# ArduHub.net
KiCad netlist of a schematic drawn in EAGLE
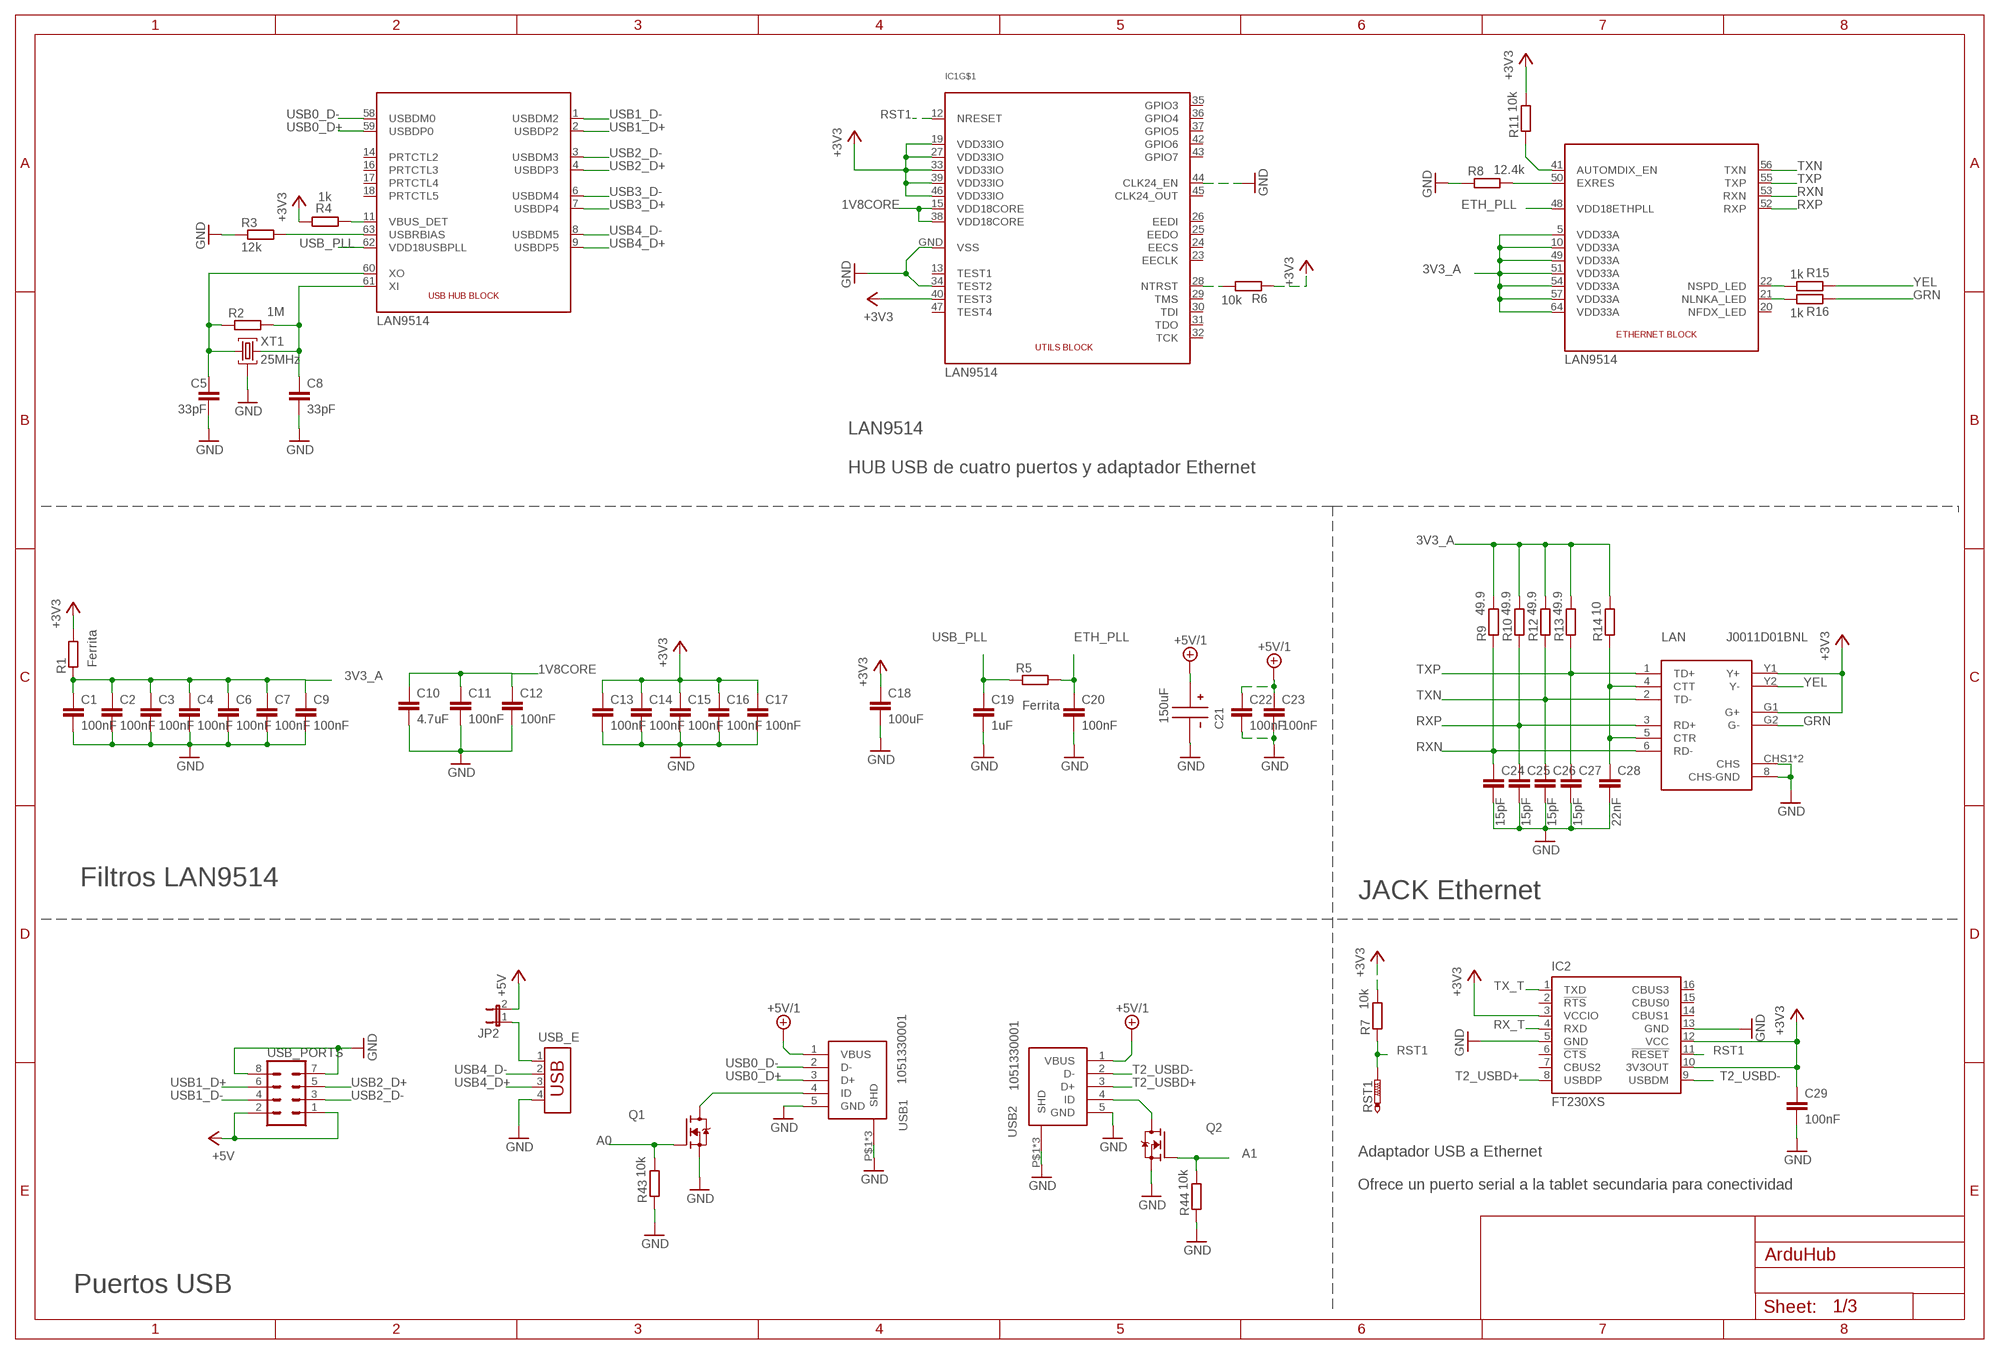
[diagram p0: schematic, sheet 1]
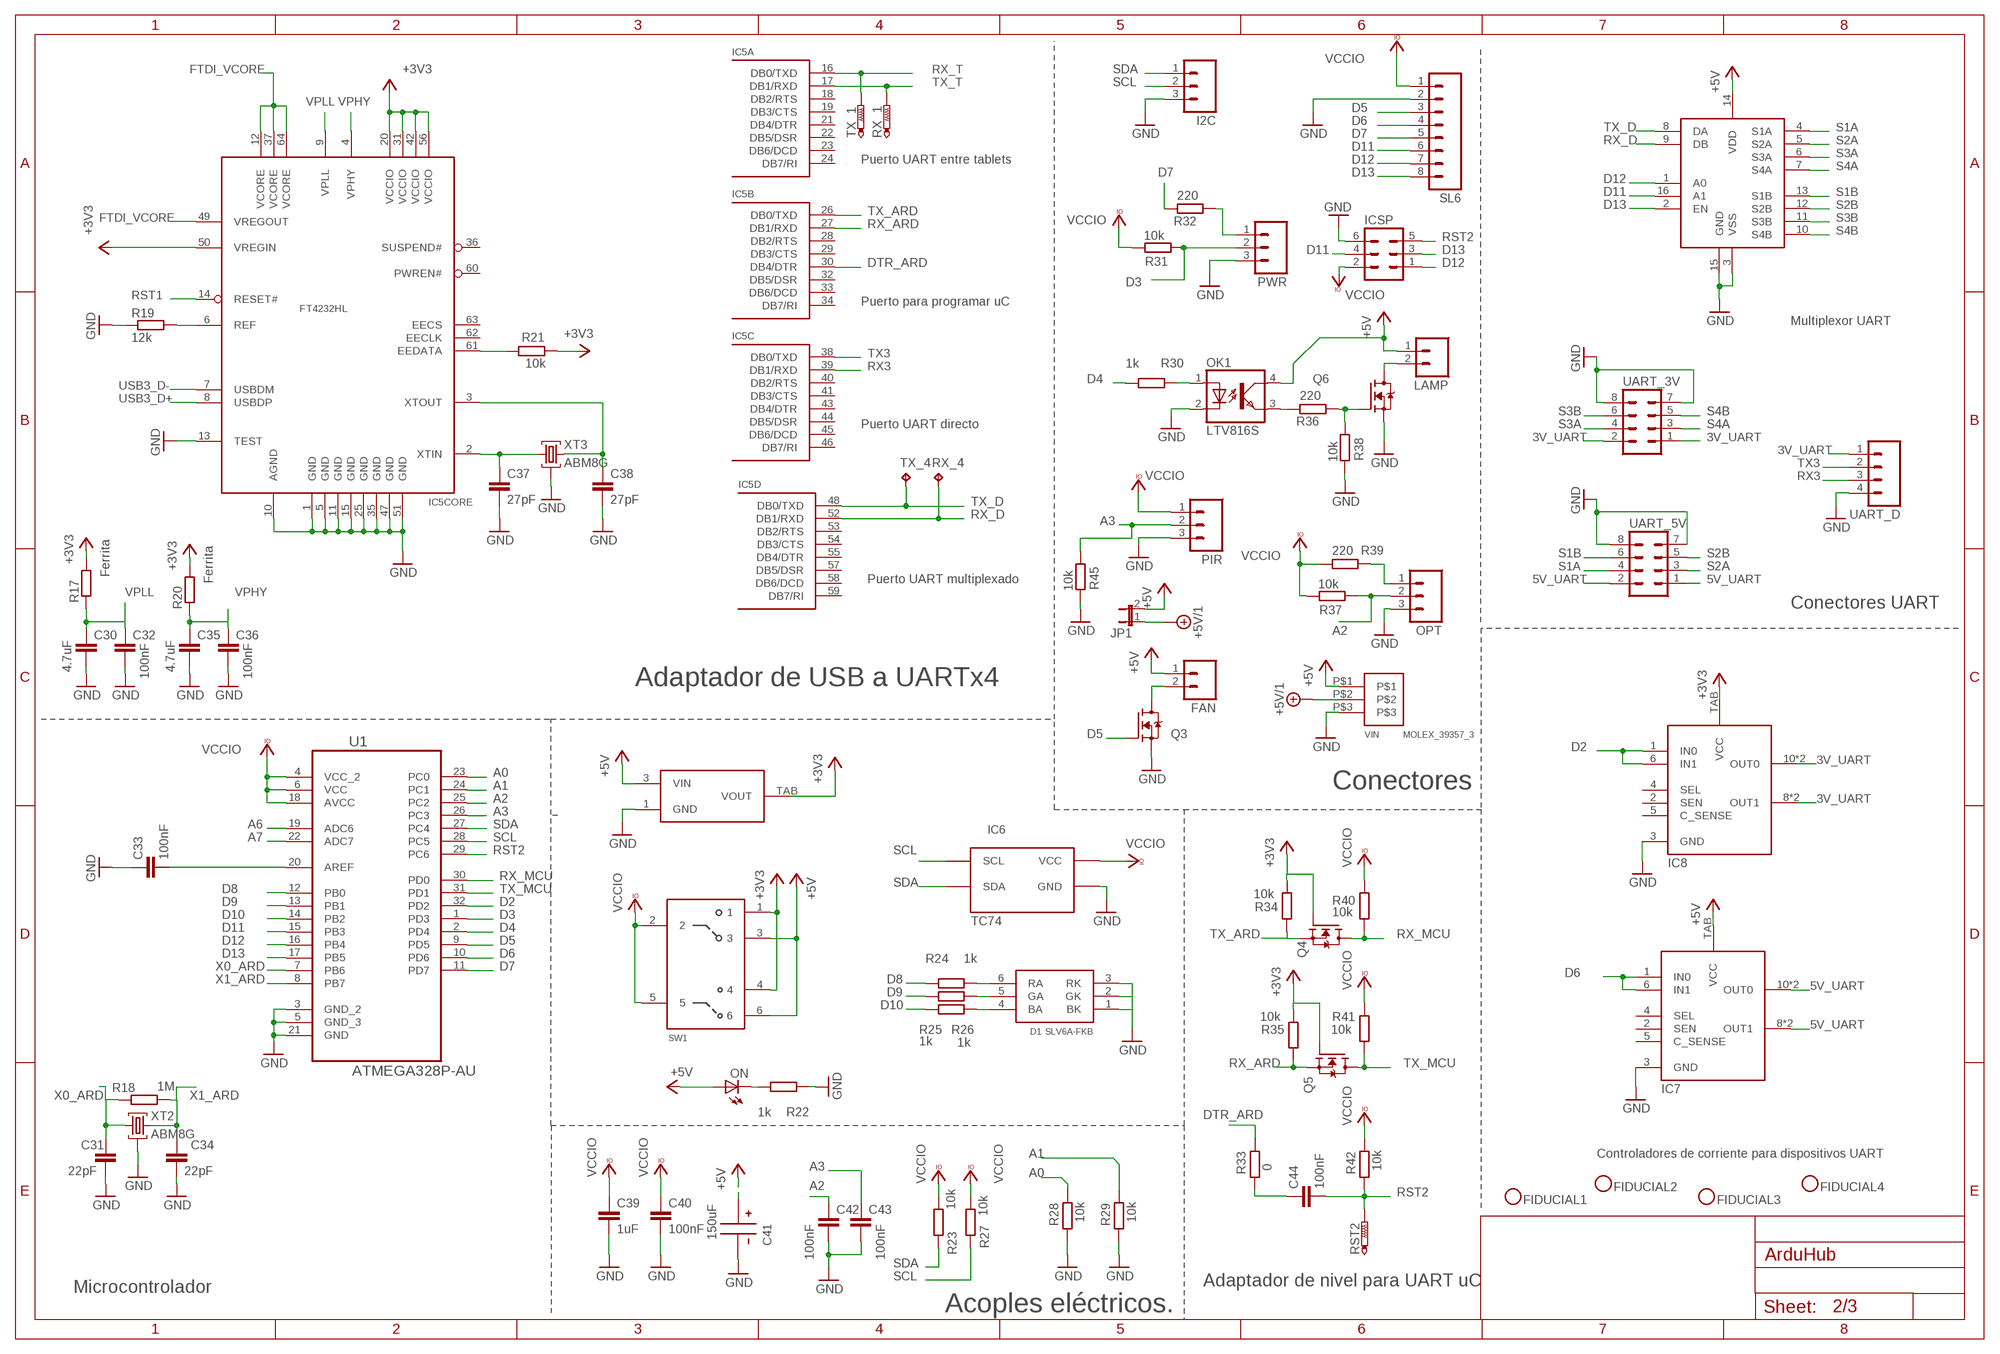
[diagram p1: schematic, sheet 2]
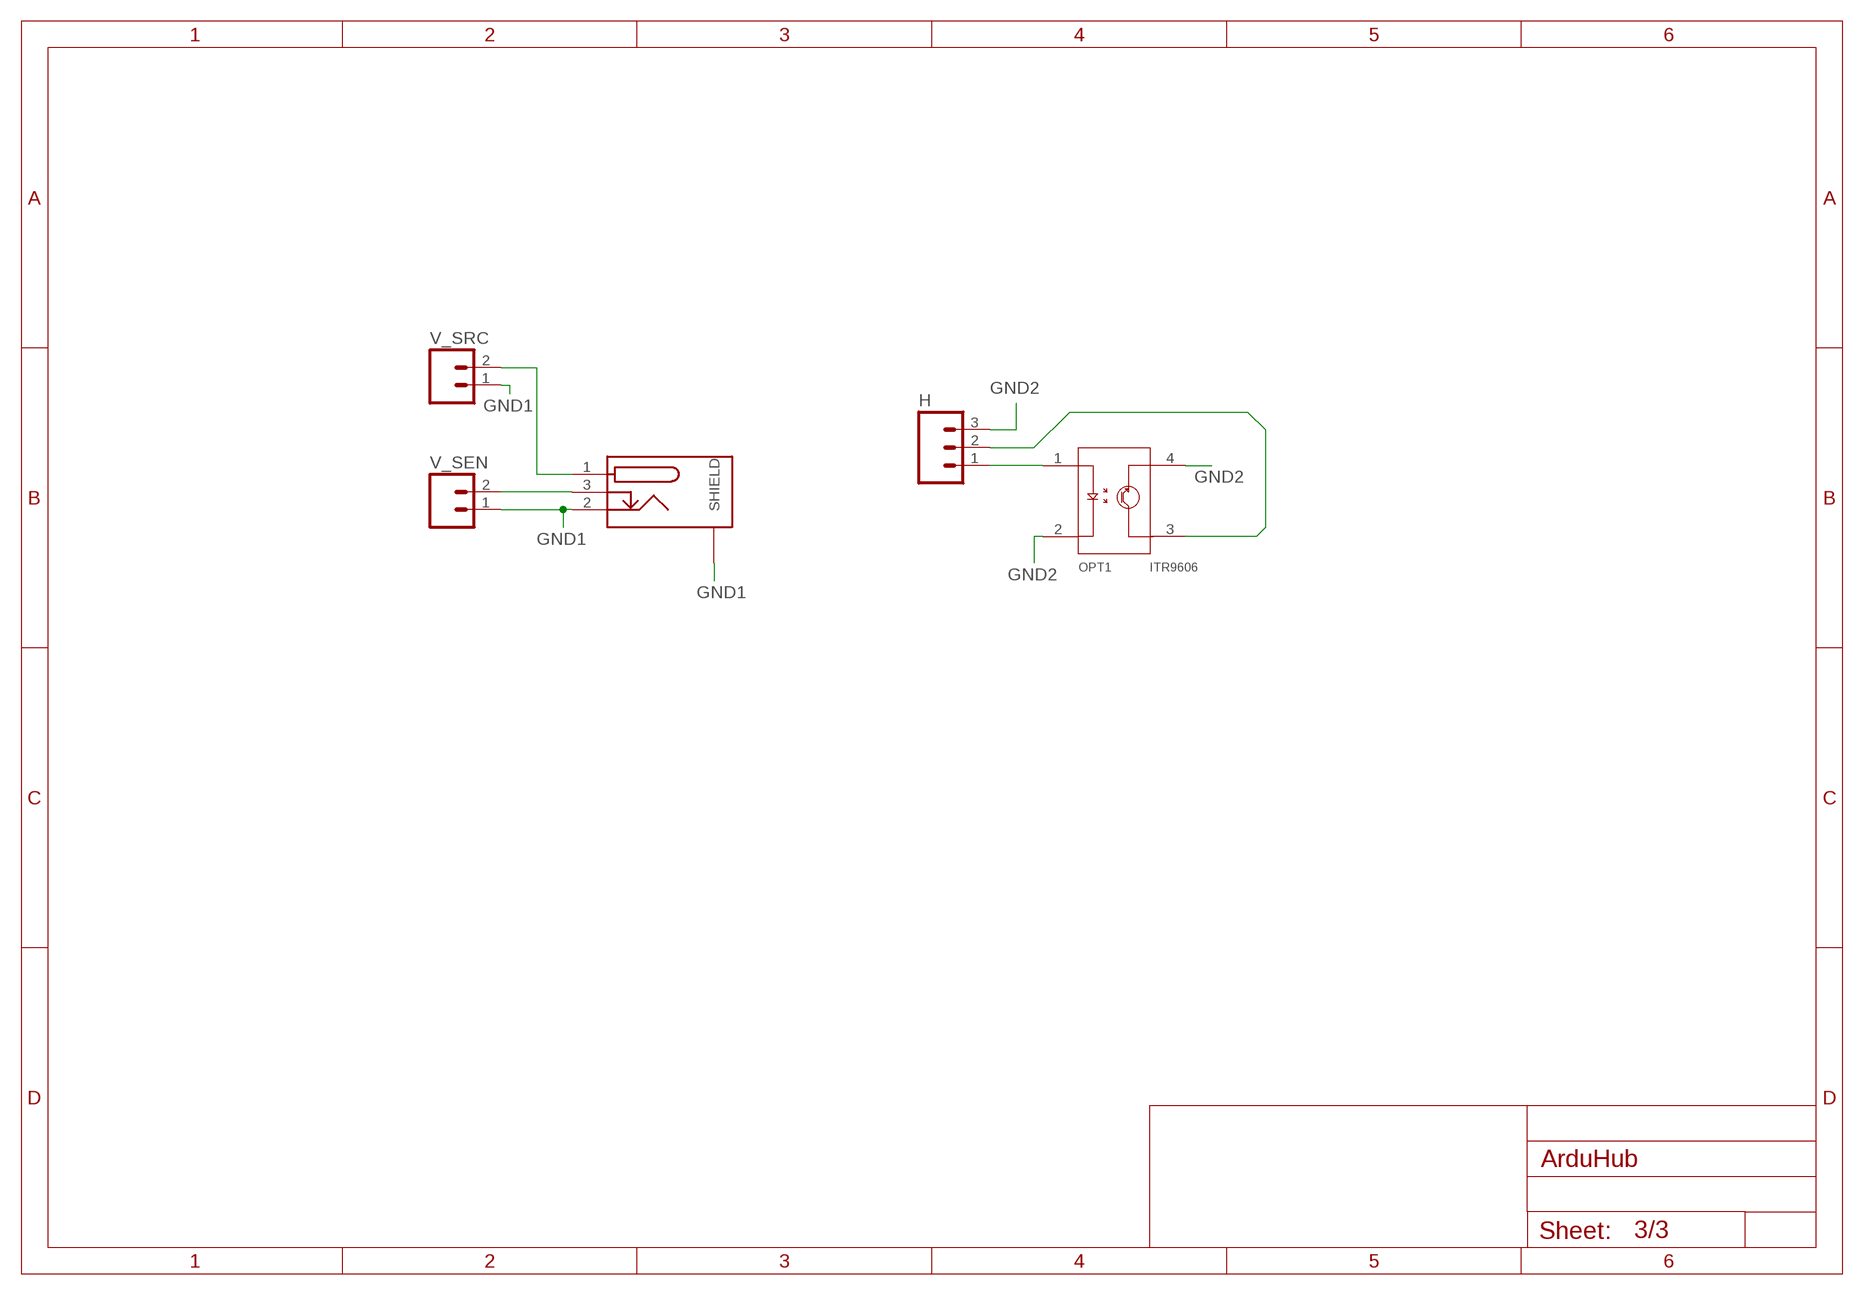
[diagram p2: schematic, sheet 3]

(export (version "E")
  (design (tool "Eeschema 10.0.6"))
  (components
    (comp (ref "C30")
      (value "4.7uF")
      (footprint "eagle-import:C0402")
      (libsource (lib "eagle-import") (part "C-EUC0402"))
    )
    (comp (ref "C31")
      (value "22pF")
      (footprint "eagle-import:C0402")
      (libsource (lib "eagle-import") (part "C-EUC0402"))
    )
    (comp (ref "C32")
      (value "100nF")
      (footprint "eagle-import:C0402")
      (libsource (lib "eagle-import") (part "C-EUC0402"))
    )
    (comp (ref "C33")
      (value "100nF")
      (footprint "eagle-import:C0402")
      (libsource (lib "eagle-import") (part "C-EUC0402"))
    )
    (comp (ref "C34")
      (value "22pF")
      (footprint "eagle-import:C0402")
      (libsource (lib "eagle-import") (part "C-EUC0402"))
    )
    (comp (ref "C35")
      (value "4.7uF")
      (footprint "eagle-import:C0402")
      (libsource (lib "eagle-import") (part "C-EUC0402"))
    )
    (comp (ref "C36")
      (value "100nF")
      (footprint "eagle-import:C0402")
      (libsource (lib "eagle-import") (part "C-EUC0402"))
    )
    (comp (ref "C37")
      (value "27pF")
      (footprint "eagle-import:C0402")
      (libsource (lib "eagle-import") (part "C-EUC0402"))
    )
    (comp (ref "C38")
      (value "27pF")
      (footprint "eagle-import:C0402")
      (libsource (lib "eagle-import") (part "C-EUC0402"))
    )
    (comp (ref "C39")
      (value "1uF")
      (footprint "eagle-import:C0402")
      (libsource (lib "eagle-import") (part "C-EUC0402"))
    )
    (comp (ref "C40")
      (value "100nF")
      (footprint "eagle-import:C0402")
      (libsource (lib "eagle-import") (part "C-EUC0402"))
    )
    (comp (ref "C41")
      (value "150uF")
      (footprint "eagle-import:MVA_CAP_F55")
      (libsource (lib "eagle-import") (part "EMVE100ADA151MF55G"))
    )
    (comp (ref "C42")
      (value "100nF")
      (footprint "eagle-import:C0402")
      (libsource (lib "eagle-import") (part "C-EUC0402"))
    )
    (comp (ref "C43")
      (value "100nF")
      (footprint "eagle-import:C0402")
      (libsource (lib "eagle-import") (part "C-EUC0402"))
    )
    (comp (ref "C44")
      (value "100nF")
      (footprint "eagle-import:C0402")
      (libsource (lib "eagle-import") (part "C-EUC0402"))
    )
    (comp (ref "D1")
      (value "SLV6A-FKB")
      (footprint "eagle-import:PLCC-6")
      (libsource (lib "eagle-import") (part "SLV6A-FKB"))
    )
    (comp (ref "FAN")
      (value "M02")
      (footprint "eagle-import:02P")
      (libsource (lib "eagle-import") (part "M02"))
    )
    (comp (ref "FIDUCIAL1")
      (value "FIDU_2C")
      (footprint "eagle-import:FIDUCIAL_TEST_2C")
      (libsource (lib "eagle-import") (part "FIDU_2C"))
    )
    (comp (ref "FIDUCIAL2")
      (value "FIDU_2C")
      (footprint "eagle-import:FIDUCIAL_TEST_2C")
      (libsource (lib "eagle-import") (part "FIDU_2C"))
    )
    (comp (ref "FIDUCIAL3")
      (value "FIDU_2C")
      (footprint "eagle-import:FIDUCIAL_TEST_2C")
      (libsource (lib "eagle-import") (part "FIDU_2C"))
    )
    (comp (ref "FIDUCIAL4")
      (value "FIDU_2C")
      (footprint "eagle-import:FIDUCIAL_TEST_2C")
      (libsource (lib "eagle-import") (part "FIDU_2C"))
    )
    (comp (ref "I2C")
      (value "M03")
      (footprint "eagle-import:03P")
      (libsource (lib "eagle-import") (part "M03"))
    )
    (comp (ref "IC4")
      (value "AP1084D")
      (footprint "eagle-import:TO_252_3")
      (libsource (lib "eagle-import") (part "AP1084D"))
    )
    (comp (ref "IC5")
      (value "FT4232HL")
      (footprint "eagle-import:LQFP64")
      (fields (field (name "REF") "FT4232HL-REEL"))
      (libsource (lib "eagle-import") (part "FT4232HL"))
    )
    (comp (ref "IC6")
      (value "TC74")
      (footprint "eagle-import:SOT-23-5")
      (libsource (lib "eagle-import") (part "TC74"))
    )
    (comp (ref "IC7")
      (value "VND7140AJ12TR")
      (footprint "eagle-import:POWERSSO-12")
      (libsource (lib "eagle-import") (part "VND7140AJ12TR"))
    )
    (comp (ref "IC8")
      (value "VND7140AJ12TR")
      (footprint "eagle-import:POWERSSO-12")
      (libsource (lib "eagle-import") (part "VND7140AJ12TR"))
    )
    (comp (ref "IC9")
      (value "MUX509IPWR")
      (footprint "eagle-import:TSSOP-16")
      (libsource (lib "eagle-import") (part "MUX509IPWR"))
    )
    (comp (ref "ICSP")
      (value "MA03-2")
      (footprint "eagle-import:MA03-2")
      (libsource (lib "eagle-import") (part "MA03-2"))
    )
    (comp (ref "JP1")
      (value "JP1E")
      (footprint "eagle-import:JP1")
      (libsource (lib "eagle-import") (part "JP1E"))
    )
    (comp (ref "LAMP")
      (value "M02")
      (footprint "eagle-import:02P")
      (libsource (lib "eagle-import") (part "M02"))
    )
    (comp (ref "OK1")
      (value "LTV816S")
      (footprint "eagle-import:SMD4")
      (libsource (lib "eagle-import") (part "LTV816S"))
    )
    (comp (ref "ON")
      (value "LED-0603")
      (footprint "eagle-import:LED-603")
      (libsource (lib "eagle-import") (part "LED-0603"))
    )
    (comp (ref "OPT")
      (value "M03")
      (footprint "eagle-import:03P")
      (libsource (lib "eagle-import") (part "M03"))
    )
    (comp (ref "PIR")
      (value "M03")
      (footprint "eagle-import:03P")
      (libsource (lib "eagle-import") (part "M03"))
    )
    (comp (ref "PWR")
      (value "M03")
      (footprint "eagle-import:03P")
      (libsource (lib "eagle-import") (part "M03"))
    )
    (comp (ref "Q3")
      (value "TRANSISTOR_FET_BS170-SOT-23")
      (footprint "eagle-import:SOT-23")
      (libsource (lib "eagle-import") (part "TRANSISTOR_FET_BS170-SOT-23"))
    )
    (comp (ref "Q4")
      (value "TRANSISTOR_FET_BS170-SOT-23")
      (footprint "eagle-import:SOT-23")
      (libsource (lib "eagle-import") (part "TRANSISTOR_FET_BS170-SOT-23"))
    )
    (comp (ref "Q5")
      (value "TRANSISTOR_FET_BS170-SOT-23")
      (footprint "eagle-import:SOT-23")
      (libsource (lib "eagle-import") (part "TRANSISTOR_FET_BS170-SOT-23"))
    )
    (comp (ref "Q6")
      (value "TRANSISTOR_FET_BS170-SOT-23")
      (footprint "eagle-import:SOT-23")
      (libsource (lib "eagle-import") (part "TRANSISTOR_FET_BS170-SOT-23"))
    )
    (comp (ref "R17")
      (value "Ferrita")
      (footprint "eagle-import:R0603")
      (libsource (lib "eagle-import") (part "R-EU_R0603"))
    )
    (comp (ref "R18")
      (value "1M")
      (footprint "eagle-import:R0402")
      (libsource (lib "eagle-import") (part "R-EU_R0402"))
    )
    (comp (ref "R19")
      (value "12k")
      (footprint "eagle-import:R0402")
      (libsource (lib "eagle-import") (part "R-EU_R0402"))
    )
    (comp (ref "R20")
      (value "Ferrita")
      (footprint "eagle-import:R0603")
      (libsource (lib "eagle-import") (part "R-EU_R0603"))
    )
    (comp (ref "R21")
      (value "10k")
      (footprint "eagle-import:R0402")
      (libsource (lib "eagle-import") (part "R-EU_R0402"))
    )
    (comp (ref "R22")
      (value "1k")
      (footprint "eagle-import:R0402")
      (libsource (lib "eagle-import") (part "R-EU_R0402"))
    )
    (comp (ref "R23")
      (value "10k")
      (footprint "eagle-import:R0402")
      (libsource (lib "eagle-import") (part "R-EU_R0402"))
    )
    (comp (ref "R24")
      (value "1k")
      (footprint "eagle-import:R0402")
      (libsource (lib "eagle-import") (part "R-EU_R0402"))
    )
    (comp (ref "R25")
      (value "1k")
      (footprint "eagle-import:R0402")
      (libsource (lib "eagle-import") (part "R-EU_R0402"))
    )
    (comp (ref "R26")
      (value "1k")
      (footprint "eagle-import:R0402")
      (libsource (lib "eagle-import") (part "R-EU_R0402"))
    )
    (comp (ref "R27")
      (value "10k")
      (footprint "eagle-import:R0402")
      (libsource (lib "eagle-import") (part "R-EU_R0402"))
    )
    (comp (ref "R28")
      (value "10k")
      (footprint "eagle-import:R0402")
      (libsource (lib "eagle-import") (part "R-EU_R0402"))
    )
    (comp (ref "R29")
      (value "10k")
      (footprint "eagle-import:R0402")
      (libsource (lib "eagle-import") (part "R-EU_R0402"))
    )
    (comp (ref "R30")
      (value "1k")
      (footprint "eagle-import:R0402")
      (libsource (lib "eagle-import") (part "R-EU_R0402"))
    )
    (comp (ref "R31")
      (value "10k")
      (footprint "eagle-import:R0402")
      (libsource (lib "eagle-import") (part "R-EU_R0402"))
    )
    (comp (ref "R32")
      (value "220")
      (footprint "eagle-import:R0402")
      (libsource (lib "eagle-import") (part "R-EU_R0402"))
    )
    (comp (ref "R33")
      (value "0")
      (footprint "eagle-import:R0402")
      (libsource (lib "eagle-import") (part "R-EU_R0402"))
    )
    (comp (ref "R34")
      (value "10k")
      (footprint "eagle-import:R0402")
      (libsource (lib "eagle-import") (part "R-EU_R0402"))
    )
    (comp (ref "R35")
      (value "10k")
      (footprint "eagle-import:R0402")
      (libsource (lib "eagle-import") (part "R-EU_R0402"))
    )
    (comp (ref "R36")
      (value "220")
      (footprint "eagle-import:R0402")
      (libsource (lib "eagle-import") (part "R-EU_R0402"))
    )
    (comp (ref "R37")
      (value "10k")
      (footprint "eagle-import:R0402")
      (libsource (lib "eagle-import") (part "R-EU_R0402"))
    )
    (comp (ref "R38")
      (value "10k")
      (footprint "eagle-import:R0402")
      (libsource (lib "eagle-import") (part "R-EU_R0402"))
    )
    (comp (ref "R39")
      (value "220")
      (footprint "eagle-import:R0402")
      (libsource (lib "eagle-import") (part "R-EU_R0402"))
    )
    (comp (ref "R40")
      (value "10k")
      (footprint "eagle-import:R0402")
      (libsource (lib "eagle-import") (part "R-EU_R0402"))
    )
    (comp (ref "R41")
      (value "10k")
      (footprint "eagle-import:R0402")
      (libsource (lib "eagle-import") (part "R-EU_R0402"))
    )
    (comp (ref "R42")
      (value "10k")
      (footprint "eagle-import:R0402")
      (libsource (lib "eagle-import") (part "R-EU_R0402"))
    )
    (comp (ref "R45")
      (value "10k")
      (footprint "eagle-import:R0402")
      (libsource (lib "eagle-import") (part "R-EU_R0402"))
    )
    (comp (ref "RST2")
      (value "PTR1TP06SQ")
      (footprint "eagle-import:TP06SQ")
      (libsource (lib "eagle-import") (part "PTR1TP06SQ"))
    )
    (comp (ref "RX_1")
      (value "PTR1TP06SQ")
      (footprint "eagle-import:TP06SQ")
      (libsource (lib "eagle-import") (part "PTR1TP06SQ"))
    )
    (comp (ref "RX_4")
      (value "TPTP06SQ")
      (footprint "eagle-import:TP06SQ")
      (libsource (lib "eagle-import") (part "TPTP06SQ"))
    )
    (comp (ref "SL6")
      (value "M08")
      (footprint "eagle-import:08P")
      (libsource (lib "eagle-import") (part "M08"))
    )
    (comp (ref "SW1")
      (value "452403012014")
      (footprint "eagle-import:452403012014")
      (libsource (lib "eagle-import") (part "452403012014"))
    )
    (comp (ref "TX_1")
      (value "PTR1TP06SQ")
      (footprint "eagle-import:TP06SQ")
      (libsource (lib "eagle-import") (part "PTR1TP06SQ"))
    )
    (comp (ref "TX_4")
      (value "TPTP06SQ")
      (footprint "eagle-import:TP06SQ")
      (libsource (lib "eagle-import") (part "TPTP06SQ"))
    )
    (comp (ref "U1")
      (value "ATMEGA328P-AU")
      (footprint "eagle-import:QFP80P900X900X120-32N")
      (libsource (lib "eagle-import") (part "ATMEGA328P-AU"))
    )
    (comp (ref "UART_3V")
      (value "MA04-2")
      (footprint "eagle-import:MA04-2")
      (libsource (lib "eagle-import") (part "MA04-2"))
    )
    (comp (ref "UART_5V")
      (value "MA04-2")
      (footprint "eagle-import:MA04-2")
      (libsource (lib "eagle-import") (part "MA04-2"))
    )
    (comp (ref "UART_D")
      (value "M04")
      (footprint "eagle-import:04P")
      (libsource (lib "eagle-import") (part "M04"))
    )
    (comp (ref "VIN")
      (value "MOLEX_39357_3")
      (footprint "eagle-import:MOLEX_39357-3")
      (libsource (lib "eagle-import") (part "MOLEX_39357_3"))
    )
    (comp (ref "XT2")
      (value "ABM8G")
      (footprint "eagle-import:ABM8G")
      (libsource (lib "eagle-import") (part "ABM8G"))
    )
    (comp (ref "XT3")
      (value "ABM8G")
      (footprint "eagle-import:ABM8G")
      (libsource (lib "eagle-import") (part "ABM8G"))
    )
    (comp (ref "H")
      (value "M03")
      (footprint "eagle-import:03P")
      (libsource (lib "eagle-import") (part "M03"))
    )
    (comp (ref "OPT1")
      (value "ITR9606")
      (footprint "eagle-import:ITR9606")
      (libsource (lib "eagle-import") (part "ITR9606"))
    )
    (comp (ref "PLUG")
      (value "PJ051A")
      (footprint "eagle-import:PJ051A")
      (libsource (lib "eagle-import") (part "PJ051A"))
    )
    (comp (ref "V_SEN")
      (value "M02")
      (footprint "eagle-import:02P")
      (libsource (lib "eagle-import") (part "M02"))
    )
    (comp (ref "V_SRC")
      (value "M02")
      (footprint "eagle-import:02P")
      (libsource (lib "eagle-import") (part "M02"))
    )
    (comp (ref "C1")
      (value "100nF")
      (footprint "eagle-import:C0402")
      (libsource (lib "eagle-import") (part "C-EUC0402"))
    )
    (comp (ref "C2")
      (value "100nF")
      (footprint "eagle-import:C0402")
      (libsource (lib "eagle-import") (part "C-EUC0402"))
    )
    (comp (ref "C3")
      (value "100nF")
      (footprint "eagle-import:C0402")
      (libsource (lib "eagle-import") (part "C-EUC0402"))
    )
    (comp (ref "C4")
      (value "100nF")
      (footprint "eagle-import:C0402")
      (libsource (lib "eagle-import") (part "C-EUC0402"))
    )
    (comp (ref "C5")
      (value "33pF")
      (footprint "eagle-import:C0402")
      (libsource (lib "eagle-import") (part "C-EUC0402"))
    )
    (comp (ref "C6")
      (value "100nF")
      (footprint "eagle-import:C0402")
      (libsource (lib "eagle-import") (part "C-EUC0402"))
    )
    (comp (ref "C7")
      (value "100nF")
      (footprint "eagle-import:C0402")
      (libsource (lib "eagle-import") (part "C-EUC0402"))
    )
    (comp (ref "C8")
      (value "33pF")
      (footprint "eagle-import:C0402")
      (libsource (lib "eagle-import") (part "C-EUC0402"))
    )
    (comp (ref "C9")
      (value "100nF")
      (footprint "eagle-import:C0402")
      (libsource (lib "eagle-import") (part "C-EUC0402"))
    )
    (comp (ref "C10")
      (value "4.7uF")
      (footprint "eagle-import:C0402")
      (libsource (lib "eagle-import") (part "C-EUC0402"))
    )
    (comp (ref "C11")
      (value "100nF")
      (footprint "eagle-import:C0402")
      (libsource (lib "eagle-import") (part "C-EUC0402"))
    )
    (comp (ref "C12")
      (value "100nF")
      (footprint "eagle-import:C0402")
      (libsource (lib "eagle-import") (part "C-EUC0402"))
    )
    (comp (ref "C13")
      (value "100nF")
      (footprint "eagle-import:C0402")
      (libsource (lib "eagle-import") (part "C-EUC0402"))
    )
    (comp (ref "C14")
      (value "100nF")
      (footprint "eagle-import:C0402")
      (libsource (lib "eagle-import") (part "C-EUC0402"))
    )
    (comp (ref "C15")
      (value "100nF")
      (footprint "eagle-import:C0402")
      (libsource (lib "eagle-import") (part "C-EUC0402"))
    )
    (comp (ref "C16")
      (value "100nF")
      (footprint "eagle-import:C0402")
      (libsource (lib "eagle-import") (part "C-EUC0402"))
    )
    (comp (ref "C17")
      (value "100nF")
      (footprint "eagle-import:C0402")
      (libsource (lib "eagle-import") (part "C-EUC0402"))
    )
    (comp (ref "C18")
      (value "100uF")
      (footprint "eagle-import:C0603")
      (libsource (lib "eagle-import") (part "C-EUC0603"))
    )
    (comp (ref "C19")
      (value "1uF")
      (footprint "eagle-import:C0402")
      (libsource (lib "eagle-import") (part "C-EUC0402"))
    )
    (comp (ref "C20")
      (value "100nF")
      (footprint "eagle-import:C0402")
      (libsource (lib "eagle-import") (part "C-EUC0402"))
    )
    (comp (ref "C21")
      (value "150uF")
      (footprint "eagle-import:MVA_CAP_F55")
      (libsource (lib "eagle-import") (part "EMVE100ADA151MF55G"))
    )
    (comp (ref "C22")
      (value "100nF")
      (footprint "eagle-import:C0402")
      (libsource (lib "eagle-import") (part "C-EUC0402"))
    )
    (comp (ref "C23")
      (value "100nF")
      (footprint "eagle-import:C0402")
      (libsource (lib "eagle-import") (part "C-EUC0402"))
    )
    (comp (ref "C24")
      (value "15pF")
      (footprint "eagle-import:C0402")
      (libsource (lib "eagle-import") (part "C-EUC0402"))
    )
    (comp (ref "C25")
      (value "15pF")
      (footprint "eagle-import:C0402")
      (libsource (lib "eagle-import") (part "C-EUC0402"))
    )
    (comp (ref "C26")
      (value "15pF")
      (footprint "eagle-import:C0402")
      (libsource (lib "eagle-import") (part "C-EUC0402"))
    )
    (comp (ref "C27")
      (value "15pF")
      (footprint "eagle-import:C0402")
      (libsource (lib "eagle-import") (part "C-EUC0402"))
    )
    (comp (ref "C28")
      (value "22nF")
      (footprint "eagle-import:C0402")
      (libsource (lib "eagle-import") (part "C-EUC0402"))
    )
    (comp (ref "C29")
      (value "100nF")
      (footprint "eagle-import:C0402")
      (libsource (lib "eagle-import") (part "C-EUC0402"))
    )
    (comp (ref "IC1")
      (value "LAN9514")
      (footprint "eagle-import:QFN64")
      (fields (field (name "REF") "LAN9514-JZX-TR"))
      (libsource (lib "eagle-import") (part "LAN9514"))
    )
    (comp (ref "IC2")
      (value "FT230XS")
      (footprint "eagle-import:SSOP16")
      (libsource (lib "eagle-import") (part "FT230XS"))
    )
    (comp (ref "JP2")
      (value "JP1E")
      (footprint "eagle-import:JP1")
      (libsource (lib "eagle-import") (part "JP1E"))
    )
    (comp (ref "LAN")
      (value "J0011D01BNL")
      (footprint "eagle-import:J0011D01BNL")
      (libsource (lib "eagle-import") (part "J0011D01BNL"))
    )
    (comp (ref "Q1")
      (value "TRANSISTOR_FET_BS170-SOT-23")
      (footprint "eagle-import:SOT-23")
      (libsource (lib "eagle-import") (part "TRANSISTOR_FET_BS170-SOT-23"))
    )
    (comp (ref "Q2")
      (value "TRANSISTOR_FET_BS170-SOT-23")
      (footprint "eagle-import:SOT-23")
      (libsource (lib "eagle-import") (part "TRANSISTOR_FET_BS170-SOT-23"))
    )
    (comp (ref "R1")
      (value "Ferrita")
      (footprint "eagle-import:R0603")
      (libsource (lib "eagle-import") (part "R-EU_R0603"))
    )
    (comp (ref "R2")
      (value "1M")
      (footprint "eagle-import:R0402")
      (libsource (lib "eagle-import") (part "R-EU_R0402"))
    )
    (comp (ref "R3")
      (value "12k")
      (footprint "eagle-import:R0402")
      (libsource (lib "eagle-import") (part "R-EU_R0402"))
    )
    (comp (ref "R4")
      (value "1k")
      (footprint "eagle-import:R0402")
      (libsource (lib "eagle-import") (part "R-EU_R0402"))
    )
    (comp (ref "R5")
      (value "Ferrita")
      (footprint "eagle-import:R0603")
      (libsource (lib "eagle-import") (part "R-EU_R0603"))
    )
    (comp (ref "R6")
      (value "10k")
      (footprint "eagle-import:R0402")
      (libsource (lib "eagle-import") (part "R-EU_R0402"))
    )
    (comp (ref "R7")
      (value "10k")
      (footprint "eagle-import:R0402")
      (libsource (lib "eagle-import") (part "R-EU_R0402"))
    )
    (comp (ref "R8")
      (value "12.4k")
      (footprint "eagle-import:R0402")
      (libsource (lib "eagle-import") (part "R-EU_R0402"))
    )
    (comp (ref "R9")
      (value "49.9")
      (footprint "eagle-import:R0402")
      (libsource (lib "eagle-import") (part "R-EU_R0402"))
    )
    (comp (ref "R10")
      (value "49.9")
      (footprint "eagle-import:R0402")
      (libsource (lib "eagle-import") (part "R-EU_R0402"))
    )
    (comp (ref "R11")
      (value "10k")
      (footprint "eagle-import:R0402")
      (libsource (lib "eagle-import") (part "R-EU_R0402"))
    )
    (comp (ref "R12")
      (value "49.9")
      (footprint "eagle-import:R0402")
      (libsource (lib "eagle-import") (part "R-EU_R0402"))
    )
    (comp (ref "R13")
      (value "49.9")
      (footprint "eagle-import:R0402")
      (libsource (lib "eagle-import") (part "R-EU_R0402"))
    )
    (comp (ref "R14")
      (value "10")
      (footprint "eagle-import:R0402")
      (libsource (lib "eagle-import") (part "R-EU_R0402"))
    )
    (comp (ref "R15")
      (value "1k")
      (footprint "eagle-import:R0402")
      (libsource (lib "eagle-import") (part "R-EU_R0402"))
    )
    (comp (ref "R16")
      (value "1k")
      (footprint "eagle-import:R0402")
      (libsource (lib "eagle-import") (part "R-EU_R0402"))
    )
    (comp (ref "R43")
      (value "10k")
      (footprint "eagle-import:R0402")
      (libsource (lib "eagle-import") (part "R-EU_R0402"))
    )
    (comp (ref "R44")
      (value "10k")
      (footprint "eagle-import:R0402")
      (libsource (lib "eagle-import") (part "R-EU_R0402"))
    )
    (comp (ref "RST1")
      (value "PTR1B1,27")
      (footprint "eagle-import:B1,27")
      (libsource (lib "eagle-import") (part "PTR1B1,27"))
    )
    (comp (ref "USB1")
      (value "1051330001")
      (footprint "eagle-import:1051330001")
      (libsource (lib "eagle-import") (part "1051330001"))
    )
    (comp (ref "USB2")
      (value "1051330001")
      (footprint "eagle-import:1051330001")
      (libsource (lib "eagle-import") (part "1051330001"))
    )
    (comp (ref "USB_E")
      (value "USB-787616")
      (footprint "eagle-import:USB")
      (libsource (lib "eagle-import") (part "USB-787616"))
    )
    (comp (ref "USB_PORTS")
      (value "MA04-2")
      (footprint "eagle-import:MA04-2")
      (libsource (lib "eagle-import") (part "MA04-2"))
    )
    (comp (ref "XT1")
      (value "25MHz")
      (footprint "eagle-import:ABM8G")
      (libsource (lib "eagle-import") (part "ABM8G"))
    )
  )
  (nets
    (net (code "1") (name "+3V3") (class "Default")
      (node (ref "C13") (pin "1") (pinfunction "1_1") (pintype "passive"))
      (node (ref "C14") (pin "1") (pinfunction "1_1") (pintype "passive"))
      (node (ref "C15") (pin "1") (pinfunction "1_1") (pintype "passive"))
      (node (ref "C16") (pin "1") (pinfunction "1_1") (pintype "passive"))
      (node (ref "C17") (pin "1") (pinfunction "1_1") (pintype "passive"))
      (node (ref "C18") (pin "1") (pinfunction "1_1") (pintype "passive"))
      (node (ref "C29") (pin "1") (pinfunction "1_1") (pintype "passive"))
      (node (ref "IC1") (pin "19") (pinfunction "VDD33IO_19") (pintype "bidirectional"))
      (node (ref "IC1") (pin "27") (pinfunction "VDD33IO_27") (pintype "bidirectional"))
      (node (ref "IC1") (pin "33") (pinfunction "VDD33IO_33") (pintype "bidirectional"))
      (node (ref "IC1") (pin "39") (pinfunction "VDD33IO_39") (pintype "bidirectional"))
      (node (ref "IC1") (pin "40") (pinfunction "TEST3_40") (pintype "bidirectional"))
      (node (ref "IC1") (pin "46") (pinfunction "VDD33IO_46") (pintype "bidirectional"))
      (node (ref "IC2") (pin "10") (pinfunction "3V3OUT_10") (pintype "output"))
      (node (ref "IC2") (pin "12") (pinfunction "VCC_12") (pintype "power_in"))
      (node (ref "IC2") (pin "3") (pinfunction "VCCIO_3") (pintype "power_in"))
      (node (ref "IC4") (pin "TAB") (pinfunction "VOUT_TAB") (pintype "bidirectional"))
      (node (ref "IC5") (pin "20") (pinfunction "VCCIO_20") (pintype "power_in"))
      (node (ref "IC5") (pin "31") (pinfunction "VCCIO_31") (pintype "power_in"))
      (node (ref "IC5") (pin "42") (pinfunction "VCCIO_42") (pintype "power_in"))
      (node (ref "IC5") (pin "50") (pinfunction "VREGIN_50") (pintype "bidirectional"))
      (node (ref "IC5") (pin "56") (pinfunction "VCCIO_56") (pintype "power_in"))
      (node (ref "IC8") (pin "TAB") (pinfunction "VCC_TAB") (pintype "bidirectional"))
      (node (ref "LAN") (pin "G1") (pinfunction "G+_G1") (pintype "bidirectional"))
      (node (ref "LAN") (pin "Y1") (pinfunction "Y+_Y1") (pintype "bidirectional"))
      (node (ref "Q4") (pin "1") (pinfunction "G_1") (pintype "passive"))
      (node (ref "Q5") (pin "1") (pinfunction "G_1") (pintype "passive"))
      (node (ref "R1") (pin "2") (pinfunction "2_2") (pintype "passive"))
      (node (ref "R11") (pin "2") (pinfunction "2_2") (pintype "passive"))
      (node (ref "R17") (pin "2") (pinfunction "2_2") (pintype "passive"))
      (node (ref "R20") (pin "2") (pinfunction "2_2") (pintype "passive"))
      (node (ref "R21") (pin "1") (pinfunction "1_1") (pintype "passive"))
      (node (ref "R34") (pin "1") (pinfunction "1_1") (pintype "passive"))
      (node (ref "R35") (pin "1") (pinfunction "1_1") (pintype "passive"))
      (node (ref "R4") (pin "2") (pinfunction "2_2") (pintype "passive"))
      (node (ref "R6") (pin "1") (pinfunction "1_1") (pintype "passive"))
      (node (ref "R7") (pin "2") (pinfunction "2_2") (pintype "passive"))
      (node (ref "SW1") (pin "1") (pinfunction "1_1") (pintype "bidirectional"))
      (node (ref "SW1") (pin "4") (pinfunction "4_4") (pintype "bidirectional"))
    )
    (net (code "2") (name "+5V") (class "Default")
      (node (ref "C41") (pin "P$+") (pinfunction "P$+_P$+") (pintype "bidirectional"))
      (node (ref "FAN") (pin "1") (pinfunction "1_1") (pintype "passive"))
      (node (ref "IC4") (pin "3") (pinfunction "VIN_3") (pintype "bidirectional"))
      (node (ref "IC7") (pin "TAB") (pinfunction "VCC_TAB") (pintype "bidirectional"))
      (node (ref "IC9") (pin "14") (pinfunction "VDD_14") (pintype "bidirectional"))
      (node (ref "JP1") (pin "2") (pinfunction "2_2") (pintype "passive"))
      (node (ref "JP2") (pin "2") (pinfunction "2_2") (pintype "passive"))
      (node (ref "LAMP") (pin "1") (pinfunction "1_1") (pintype "passive"))
      (node (ref "OK1") (pin "4") (pinfunction "COL_4") (pintype "passive"))
      (node (ref "ON") (pin "A") (pinfunction "A_A") (pintype "passive"))
      (node (ref "SW1") (pin "3") (pinfunction "3_3") (pintype "bidirectional"))
      (node (ref "SW1") (pin "6") (pinfunction "6_6") (pintype "bidirectional"))
      (node (ref "USB_PORTS") (pin "1") (pinfunction "1_1") (pintype "passive"))
      (node (ref "USB_PORTS") (pin "2") (pinfunction "2_2") (pintype "passive"))
      (node (ref "VIN") (pin "P$1") (pinfunction "P$1_P$1") (pintype "bidirectional"))
    )
    (net (code "3") (name "+5V{slash}1") (class "Default")
      (node (ref "C21") (pin "P$+") (pinfunction "P$+_P$+") (pintype "bidirectional"))
      (node (ref "C22") (pin "1") (pinfunction "1_1") (pintype "passive"))
      (node (ref "C23") (pin "1") (pinfunction "1_1") (pintype "passive"))
      (node (ref "JP1") (pin "1") (pinfunction "1_1") (pintype "passive"))
      (node (ref "USB1") (pin "1") (pinfunction "VBUS_1") (pintype "bidirectional"))
      (node (ref "USB2") (pin "1") (pinfunction "VBUS_1") (pintype "bidirectional"))
      (node (ref "VIN") (pin "P$2") (pinfunction "P$2_P$2") (pintype "bidirectional"))
    )
    (net (code "4") (name "1V8CORE") (class "Default")
      (node (ref "C10") (pin "1") (pinfunction "1_1") (pintype "passive"))
      (node (ref "C11") (pin "1") (pinfunction "1_1") (pintype "passive"))
      (node (ref "C12") (pin "1") (pinfunction "1_1") (pintype "passive"))
      (node (ref "IC1") (pin "15") (pinfunction "VDD18CORE_15") (pintype "bidirectional"))
      (node (ref "IC1") (pin "38") (pinfunction "VDD18CORE_38") (pintype "bidirectional"))
    )
    (net (code "5") (name "3V3_A") (class "Default")
      (node (ref "C1") (pin "1") (pinfunction "1_1") (pintype "passive"))
      (node (ref "C2") (pin "1") (pinfunction "1_1") (pintype "passive"))
      (node (ref "C3") (pin "1") (pinfunction "1_1") (pintype "passive"))
      (node (ref "C4") (pin "1") (pinfunction "1_1") (pintype "passive"))
      (node (ref "C6") (pin "1") (pinfunction "1_1") (pintype "passive"))
      (node (ref "C7") (pin "1") (pinfunction "1_1") (pintype "passive"))
      (node (ref "C9") (pin "1") (pinfunction "1_1") (pintype "passive"))
      (node (ref "IC1") (pin "10") (pinfunction "VDD33A_10") (pintype "bidirectional"))
      (node (ref "IC1") (pin "49") (pinfunction "VDD33A_49") (pintype "bidirectional"))
      (node (ref "IC1") (pin "5") (pinfunction "VDD33A_5") (pintype "bidirectional"))
      (node (ref "IC1") (pin "51") (pinfunction "VDD33A_51") (pintype "bidirectional"))
      (node (ref "IC1") (pin "54") (pinfunction "VDD33A_54") (pintype "bidirectional"))
      (node (ref "IC1") (pin "57") (pinfunction "VDD33A_57") (pintype "bidirectional"))
      (node (ref "IC1") (pin "64") (pinfunction "VDD33A_64") (pintype "bidirectional"))
      (node (ref "R1") (pin "1") (pinfunction "1_1") (pintype "passive"))
      (node (ref "R10") (pin "2") (pinfunction "2_2") (pintype "passive"))
      (node (ref "R12") (pin "2") (pinfunction "2_2") (pintype "passive"))
      (node (ref "R13") (pin "2") (pinfunction "2_2") (pintype "passive"))
      (node (ref "R14") (pin "2") (pinfunction "2_2") (pintype "passive"))
      (node (ref "R9") (pin "2") (pinfunction "2_2") (pintype "passive"))
    )
    (net (code "6") (name "3V_UART") (class "Default")
      (node (ref "IC8") (pin "10") (pinfunction "OUT0_10") (pintype "bidirectional"))
      (node (ref "IC8") (pin "11") (pinfunction "OUT0_11") (pintype "bidirectional"))
      (node (ref "IC8") (pin "8") (pinfunction "OUT1_8") (pintype "bidirectional"))
      (node (ref "IC8") (pin "9") (pinfunction "OUT1_9") (pintype "bidirectional"))
      (node (ref "UART_3V") (pin "1") (pinfunction "1_1") (pintype "passive"))
      (node (ref "UART_3V") (pin "2") (pinfunction "2_2") (pintype "passive"))
      (node (ref "UART_D") (pin "1") (pinfunction "1_1") (pintype "passive"))
    )
    (net (code "7") (name "5V_UART") (class "Default")
      (node (ref "IC7") (pin "10") (pinfunction "OUT0_10") (pintype "bidirectional"))
      (node (ref "IC7") (pin "11") (pinfunction "OUT0_11") (pintype "bidirectional"))
      (node (ref "IC7") (pin "8") (pinfunction "OUT1_8") (pintype "bidirectional"))
      (node (ref "IC7") (pin "9") (pinfunction "OUT1_9") (pintype "bidirectional"))
      (node (ref "UART_5V") (pin "1") (pinfunction "1_1") (pintype "passive"))
      (node (ref "UART_5V") (pin "2") (pinfunction "2_2") (pintype "passive"))
    )
    (net (code "8") (name "A0") (class "Default")
      (node (ref "Q1") (pin "1") (pinfunction "G_1") (pintype "passive"))
      (node (ref "R28") (pin "1") (pinfunction "1_1") (pintype "passive"))
      (node (ref "R43") (pin "2") (pinfunction "2_2") (pintype "passive"))
      (node (ref "U1") (pin "23") (pinfunction "PC0_23") (pintype "bidirectional"))
    )
    (net (code "9") (name "A1") (class "Default")
      (node (ref "Q2") (pin "1") (pinfunction "G_1") (pintype "passive"))
      (node (ref "R29") (pin "1") (pinfunction "1_1") (pintype "passive"))
      (node (ref "R44") (pin "2") (pinfunction "2_2") (pintype "passive"))
      (node (ref "U1") (pin "24") (pinfunction "PC1_24") (pintype "bidirectional"))
    )
    (net (code "10") (name "A2") (class "Default")
      (node (ref "C42") (pin "1") (pinfunction "1_1") (pintype "passive"))
      (node (ref "OPT") (pin "2") (pinfunction "2_2") (pintype "passive"))
      (node (ref "R37") (pin "2") (pinfunction "2_2") (pintype "passive"))
      (node (ref "U1") (pin "25") (pinfunction "PC2_25") (pintype "bidirectional"))
    )
    (net (code "11") (name "A3") (class "Default")
      (node (ref "C43") (pin "1") (pinfunction "1_1") (pintype "passive"))
      (node (ref "PIR") (pin "2") (pinfunction "2_2") (pintype "passive"))
      (node (ref "R45") (pin "2") (pinfunction "2_2") (pintype "passive"))
      (node (ref "U1") (pin "26") (pinfunction "PC3_26") (pintype "bidirectional"))
    )
    (net (code "12") (name "A6") (class "Default")
      (node (ref "U1") (pin "19") (pinfunction "ADC6_19") (pintype "input"))
    )
    (net (code "13") (name "A7") (class "Default")
      (node (ref "U1") (pin "22") (pinfunction "ADC7_22") (pintype "input"))
    )
    (net (code "14") (name "D2") (class "Default")
      (node (ref "IC8") (pin "1") (pinfunction "IN0_1") (pintype "bidirectional"))
      (node (ref "IC8") (pin "6") (pinfunction "IN1_6") (pintype "bidirectional"))
      (node (ref "U1") (pin "32") (pinfunction "PD2_32") (pintype "bidirectional"))
    )
    (net (code "15") (name "D3") (class "Default")
      (node (ref "PWR") (pin "2") (pinfunction "2_2") (pintype "passive"))
      (node (ref "R31") (pin "2") (pinfunction "2_2") (pintype "passive"))
      (node (ref "U1") (pin "1") (pinfunction "PD3_1") (pintype "bidirectional"))
    )
    (net (code "16") (name "D4") (class "Default")
      (node (ref "R30") (pin "2") (pinfunction "2_2") (pintype "passive"))
      (node (ref "U1") (pin "2") (pinfunction "PD4_2") (pintype "bidirectional"))
    )
    (net (code "17") (name "D5") (class "Default")
      (node (ref "Q3") (pin "1") (pinfunction "G_1") (pintype "passive"))
      (node (ref "SL6") (pin "3") (pinfunction "3_3") (pintype "passive"))
      (node (ref "U1") (pin "9") (pinfunction "PD5_9") (pintype "bidirectional"))
    )
    (net (code "18") (name "D6") (class "Default")
      (node (ref "IC7") (pin "1") (pinfunction "IN0_1") (pintype "bidirectional"))
      (node (ref "IC7") (pin "6") (pinfunction "IN1_6") (pintype "bidirectional"))
      (node (ref "SL6") (pin "4") (pinfunction "4_4") (pintype "passive"))
      (node (ref "U1") (pin "10") (pinfunction "PD6_10") (pintype "bidirectional"))
    )
    (net (code "19") (name "D7") (class "Default")
      (node (ref "R32") (pin "2") (pinfunction "2_2") (pintype "passive"))
      (node (ref "SL6") (pin "5") (pinfunction "5_5") (pintype "passive"))
      (node (ref "U1") (pin "11") (pinfunction "PD7_11") (pintype "bidirectional"))
    )
    (net (code "20") (name "D8") (class "Default")
      (node (ref "R24") (pin "1") (pinfunction "1_1") (pintype "passive"))
      (node (ref "U1") (pin "12") (pinfunction "PB0_12") (pintype "bidirectional"))
    )
    (net (code "21") (name "D9") (class "Default")
      (node (ref "R25") (pin "1") (pinfunction "1_1") (pintype "passive"))
      (node (ref "U1") (pin "13") (pinfunction "PB1_13") (pintype "bidirectional"))
    )
    (net (code "22") (name "D10") (class "Default")
      (node (ref "R26") (pin "1") (pinfunction "1_1") (pintype "passive"))
      (node (ref "U1") (pin "14") (pinfunction "PB2_14") (pintype "bidirectional"))
    )
    (net (code "23") (name "D11") (class "Default")
      (node (ref "IC9") (pin "16") (pinfunction "A1_16") (pintype "bidirectional"))
      (node (ref "ICSP") (pin "4") (pinfunction "4_4") (pintype "passive"))
      (node (ref "SL6") (pin "6") (pinfunction "6_6") (pintype "passive"))
      (node (ref "U1") (pin "15") (pinfunction "PB3_15") (pintype "bidirectional"))
    )
    (net (code "24") (name "D12") (class "Default")
      (node (ref "IC9") (pin "1") (pinfunction "A0_1") (pintype "bidirectional"))
      (node (ref "ICSP") (pin "1") (pinfunction "1_1") (pintype "passive"))
      (node (ref "SL6") (pin "7") (pinfunction "7_7") (pintype "passive"))
      (node (ref "U1") (pin "16") (pinfunction "PB4_16") (pintype "bidirectional"))
    )
    (net (code "25") (name "D13") (class "Default")
      (node (ref "IC9") (pin "2") (pinfunction "EN_2") (pintype "bidirectional"))
      (node (ref "ICSP") (pin "3") (pinfunction "3_3") (pintype "passive"))
      (node (ref "SL6") (pin "8") (pinfunction "8_8") (pintype "passive"))
      (node (ref "U1") (pin "17") (pinfunction "PB5_17") (pintype "bidirectional"))
    )
    (net (code "26") (name "DTR_ARD") (class "Default")
      (node (ref "IC5") (pin "30") (pinfunction "DB4/DTR_30") (pintype "bidirectional"))
      (node (ref "R33") (pin "1") (pinfunction "1_1") (pintype "passive"))
    )
    (net (code "27") (name "ETH_PLL") (class "Default")
      (node (ref "C20") (pin "1") (pinfunction "1_1") (pintype "passive"))
      (node (ref "IC1") (pin "48") (pinfunction "VDD18ETHPLL_48") (pintype "bidirectional"))
      (node (ref "R5") (pin "2") (pinfunction "2_2") (pintype "passive"))
    )
    (net (code "28") (name "FTDI_VCORE") (class "Default")
      (node (ref "IC5") (pin "12") (pinfunction "VCORE_12") (pintype "power_in"))
      (node (ref "IC5") (pin "37") (pinfunction "VCORE_37") (pintype "power_in"))
      (node (ref "IC5") (pin "49") (pinfunction "VREGOUT_49") (pintype "output"))
      (node (ref "IC5") (pin "64") (pinfunction "VCORE_64") (pintype "power_in"))
    )
    (net (code "29") (name "GND") (class "Default")
      (node (ref "C1") (pin "2") (pinfunction "2_2") (pintype "passive"))
      (node (ref "C10") (pin "2") (pinfunction "2_2") (pintype "passive"))
      (node (ref "C11") (pin "2") (pinfunction "2_2") (pintype "passive"))
      (node (ref "C12") (pin "2") (pinfunction "2_2") (pintype "passive"))
      (node (ref "C13") (pin "2") (pinfunction "2_2") (pintype "passive"))
      (node (ref "C14") (pin "2") (pinfunction "2_2") (pintype "passive"))
      (node (ref "C15") (pin "2") (pinfunction "2_2") (pintype "passive"))
      (node (ref "C16") (pin "2") (pinfunction "2_2") (pintype "passive"))
      (node (ref "C17") (pin "2") (pinfunction "2_2") (pintype "passive"))
      (node (ref "C18") (pin "2") (pinfunction "2_2") (pintype "passive"))
      (node (ref "C19") (pin "2") (pinfunction "2_2") (pintype "passive"))
      (node (ref "C2") (pin "2") (pinfunction "2_2") (pintype "passive"))
      (node (ref "C20") (pin "2") (pinfunction "2_2") (pintype "passive"))
      (node (ref "C21") (pin "P$-") (pinfunction "P$-_P$-") (pintype "bidirectional"))
      (node (ref "C22") (pin "2") (pinfunction "2_2") (pintype "passive"))
      (node (ref "C23") (pin "2") (pinfunction "2_2") (pintype "passive"))
      (node (ref "C24") (pin "2") (pinfunction "2_2") (pintype "passive"))
      (node (ref "C25") (pin "2") (pinfunction "2_2") (pintype "passive"))
      (node (ref "C26") (pin "2") (pinfunction "2_2") (pintype "passive"))
      (node (ref "C27") (pin "2") (pinfunction "2_2") (pintype "passive"))
      (node (ref "C28") (pin "2") (pinfunction "2_2") (pintype "passive"))
      (node (ref "C29") (pin "2") (pinfunction "2_2") (pintype "passive"))
      (node (ref "C3") (pin "2") (pinfunction "2_2") (pintype "passive"))
      (node (ref "C30") (pin "2") (pinfunction "2_2") (pintype "passive"))
      (node (ref "C31") (pin "2") (pinfunction "2_2") (pintype "passive"))
      (node (ref "C32") (pin "2") (pinfunction "2_2") (pintype "passive"))
      (node (ref "C33") (pin "1") (pinfunction "1_1") (pintype "passive"))
      (node (ref "C34") (pin "2") (pinfunction "2_2") (pintype "passive"))
      (node (ref "C35") (pin "2") (pinfunction "2_2") (pintype "passive"))
      (node (ref "C36") (pin "2") (pinfunction "2_2") (pintype "passive"))
      (node (ref "C37") (pin "2") (pinfunction "2_2") (pintype "passive"))
      (node (ref "C38") (pin "2") (pinfunction "2_2") (pintype "passive"))
      (node (ref "C39") (pin "2") (pinfunction "2_2") (pintype "passive"))
      (node (ref "C4") (pin "2") (pinfunction "2_2") (pintype "passive"))
      (node (ref "C40") (pin "2") (pinfunction "2_2") (pintype "passive"))
      (node (ref "C41") (pin "P$-") (pinfunction "P$-_P$-") (pintype "bidirectional"))
      (node (ref "C42") (pin "2") (pinfunction "2_2") (pintype "passive"))
      (node (ref "C43") (pin "2") (pinfunction "2_2") (pintype "passive"))
      (node (ref "C5") (pin "2") (pinfunction "2_2") (pintype "passive"))
      (node (ref "C6") (pin "2") (pinfunction "2_2") (pintype "passive"))
      (node (ref "C7") (pin "2") (pinfunction "2_2") (pintype "passive"))
      (node (ref "C8") (pin "2") (pinfunction "2_2") (pintype "passive"))
      (node (ref "C9") (pin "2") (pinfunction "2_2") (pintype "passive"))
      (node (ref "D1") (pin "1") (pinfunction "BK_1") (pintype "bidirectional"))
      (node (ref "D1") (pin "2") (pinfunction "GK_2") (pintype "bidirectional"))
      (node (ref "D1") (pin "3") (pinfunction "RK_3") (pintype "bidirectional"))
      (node (ref "I2C") (pin "3") (pinfunction "3_3") (pintype "passive"))
      (node (ref "IC1") (pin "34") (pinfunction "TEST2_34") (pintype "bidirectional"))
      (node (ref "IC1") (pin "44") (pinfunction "CLK24_EN_44") (pintype "bidirectional"))
      (node (ref "IC1") (pin "GND") (pinfunction "VSS_GND") (pintype "bidirectional"))
      (node (ref "IC2") (pin "13") (pinfunction "GND_13") (pintype "power_in"))
      (node (ref "IC2") (pin "5") (pinfunction "GND_5") (pintype "power_in"))
      (node (ref "IC4") (pin "1") (pinfunction "GND_1") (pintype "bidirectional"))
      (node (ref "IC5") (pin "1") (pinfunction "GND_1") (pintype "power_in"))
      (node (ref "IC5") (pin "10") (pinfunction "AGND_10") (pintype "power_in"))
      (node (ref "IC5") (pin "11") (pinfunction "GND_11") (pintype "power_in"))
      (node (ref "IC5") (pin "13") (pinfunction "TEST_13") (pintype "input"))
      (node (ref "IC5") (pin "15") (pinfunction "GND_15") (pintype "power_in"))
      (node (ref "IC5") (pin "25") (pinfunction "GND_25") (pintype "power_in"))
      (node (ref "IC5") (pin "35") (pinfunction "GND_35") (pintype "power_in"))
      (node (ref "IC5") (pin "47") (pinfunction "GND_47") (pintype "power_in"))
      (node (ref "IC5") (pin "5") (pinfunction "GND_5") (pintype "power_in"))
      (node (ref "IC5") (pin "51") (pinfunction "GND_51") (pintype "power_in"))
      (node (ref "IC6") (pin "2") (pinfunction "GND_2") (pintype "bidirectional"))
      (node (ref "IC7") (pin "3") (pinfunction "GND_3") (pintype "bidirectional"))
      (node (ref "IC8") (pin "3") (pinfunction "GND_3") (pintype "bidirectional"))
      (node (ref "IC9") (pin "15") (pinfunction "GND_15") (pintype "bidirectional"))
      (node (ref "IC9") (pin "3") (pinfunction "VSS_3") (pintype "bidirectional"))
      (node (ref "ICSP") (pin "6") (pinfunction "6_6") (pintype "passive"))
      (node (ref "LAN") (pin "8") (pinfunction "CHS-GND_8") (pintype "bidirectional"))
      (node (ref "LAN") (pin "CHS1") (pinfunction "CHS_CHS1") (pintype "bidirectional"))
      (node (ref "LAN") (pin "CHS2") (pinfunction "CHS_CHS2") (pintype "bidirectional"))
      (node (ref "OK1") (pin "2") (pinfunction "C_2") (pintype "passive"))
      (node (ref "OPT") (pin "3") (pinfunction "3_3") (pintype "passive"))
      (node (ref "PIR") (pin "3") (pinfunction "3_3") (pintype "passive"))
      (node (ref "PWR") (pin "3") (pinfunction "3_3") (pintype "passive"))
      (node (ref "Q1") (pin "2") (pinfunction "S_2") (pintype "passive"))
      (node (ref "Q2") (pin "2") (pinfunction "S_2") (pintype "passive"))
      (node (ref "Q3") (pin "2") (pinfunction "S_2") (pintype "passive"))
      (node (ref "Q6") (pin "2") (pinfunction "S_2") (pintype "passive"))
      (node (ref "R19") (pin "1") (pinfunction "1_1") (pintype "passive"))
      (node (ref "R22") (pin "1") (pinfunction "1_1") (pintype "passive"))
      (node (ref "R28") (pin "2") (pinfunction "2_2") (pintype "passive"))
      (node (ref "R29") (pin "2") (pinfunction "2_2") (pintype "passive"))
      (node (ref "R3") (pin "1") (pinfunction "1_1") (pintype "passive"))
      (node (ref "R38") (pin "1") (pinfunction "1_1") (pintype "passive"))
      (node (ref "R43") (pin "1") (pinfunction "1_1") (pintype "passive"))
      (node (ref "R44") (pin "1") (pinfunction "1_1") (pintype "passive"))
      (node (ref "R45") (pin "1") (pinfunction "1_1") (pintype "passive"))
      (node (ref "R8") (pin "1") (pinfunction "1_1") (pintype "passive"))
      (node (ref "SL6") (pin "2") (pinfunction "2_2") (pintype "passive"))
      (node (ref "U1") (pin "21") (pinfunction "GND_21") (pintype "passive"))
      (node (ref "U1") (pin "3") (pinfunction "GND_2_3") (pintype "passive"))
      (node (ref "U1") (pin "5") (pinfunction "GND_3_5") (pintype "passive"))
      (node (ref "UART_3V") (pin "7") (pinfunction "7_7") (pintype "passive"))
      (node (ref "UART_3V") (pin "8") (pinfunction "8_8") (pintype "passive"))
      (node (ref "UART_5V") (pin "7") (pinfunction "7_7") (pintype "passive"))
      (node (ref "UART_5V") (pin "8") (pinfunction "8_8") (pintype "passive"))
      (node (ref "UART_D") (pin "4") (pinfunction "4_4") (pintype "passive"))
      (node (ref "USB1") (pin "5") (pinfunction "GND_5") (pintype "bidirectional"))
      (node (ref "USB1") (pin "P$1") (pinfunction "SHD_P$1") (pintype "bidirectional"))
      (node (ref "USB1") (pin "P$2") (pinfunction "SHD_P$2") (pintype "bidirectional"))
      (node (ref "USB1") (pin "P$3") (pinfunction "SHD_P$3") (pintype "bidirectional"))
      (node (ref "USB2") (pin "5") (pinfunction "GND_5") (pintype "bidirectional"))
      (node (ref "USB2") (pin "P$1") (pinfunction "SHD_P$1") (pintype "bidirectional"))
      (node (ref "USB2") (pin "P$2") (pinfunction "SHD_P$2") (pintype "bidirectional"))
      (node (ref "USB2") (pin "P$3") (pinfunction "SHD_P$3") (pintype "bidirectional"))
      (node (ref "USB_E") (pin "4") (pinfunction "4_4") (pintype "passive"))
      (node (ref "USB_PORTS") (pin "7") (pinfunction "7_7") (pintype "passive"))
      (node (ref "USB_PORTS") (pin "8") (pinfunction "8_8") (pintype "passive"))
      (node (ref "VIN") (pin "P$3") (pinfunction "P$3_P$3") (pintype "bidirectional"))
      (node (ref "XT1") (pin "2") (pinfunction "2_2") (pintype "passive"))
      (node (ref "XT1") (pin "4") (pinfunction "2_4") (pintype "passive"))
      (node (ref "XT2") (pin "2") (pinfunction "2_2") (pintype "passive"))
      (node (ref "XT2") (pin "4") (pinfunction "2_4") (pintype "passive"))
      (node (ref "XT3") (pin "2") (pinfunction "2_2") (pintype "passive"))
      (node (ref "XT3") (pin "4") (pinfunction "2_4") (pintype "passive"))
    )
    (net (code "30") (name "GND1") (class "Default")
      (node (ref "PLUG") (pin "2") (pinfunction "2_2") (pintype "bidirectional"))
      (node (ref "PLUG") (pin "P$1") (pinfunction "SHIELD_P$1") (pintype "bidirectional"))
      (node (ref "PLUG") (pin "P$2") (pinfunction "SHIELD_P$2") (pintype "bidirectional"))
      (node (ref "V_SEN") (pin "1") (pinfunction "1_1") (pintype "passive"))
      (node (ref "V_SRC") (pin "1") (pinfunction "1_1") (pintype "passive"))
    )
    (net (code "31") (name "GND2") (class "Default")
      (node (ref "H") (pin "3") (pinfunction "3_3") (pintype "passive"))
      (node (ref "OPT1") (pin "2") (pinfunction "P$2_2") (pintype "bidirectional"))
      (node (ref "OPT1") (pin "4") (pinfunction "P$4_4") (pintype "bidirectional"))
    )
    (net (code "32") (name "GRN") (class "Default")
      (node (ref "LAN") (pin "G2") (pinfunction "G-_G2") (pintype "bidirectional"))
      (node (ref "R16") (pin "1") (pinfunction "1_1") (pintype "passive"))
    )
    (net (code "33") (name "Net-(C44-Pad1)") (class "Default")
      (node (ref "C44") (pin "1") (pinfunction "1_1") (pintype "passive"))
      (node (ref "R33") (pin "2") (pinfunction "2_2") (pintype "passive"))
    )
    (net (code "34") (name "Net-(D1-BA)") (class "Default")
      (node (ref "D1") (pin "4") (pinfunction "BA_4") (pintype "bidirectional"))
      (node (ref "R26") (pin "2") (pinfunction "2_2") (pintype "passive"))
    )
    (net (code "35") (name "Net-(D1-GA)") (class "Default")
      (node (ref "D1") (pin "5") (pinfunction "GA_5") (pintype "bidirectional"))
      (node (ref "R25") (pin "2") (pinfunction "2_2") (pintype "passive"))
    )
    (net (code "36") (name "Net-(D1-RA)") (class "Default")
      (node (ref "D1") (pin "6") (pinfunction "RA_6") (pintype "bidirectional"))
      (node (ref "R24") (pin "2") (pinfunction "2_2") (pintype "passive"))
    )
    (net (code "37") (name "Net-(IC1A-NTRST)") (class "Default")
      (node (ref "IC1") (pin "28") (pinfunction "NTRST_28") (pintype "bidirectional"))
      (node (ref "R6") (pin "2") (pinfunction "2_2") (pintype "passive"))
    )
    (net (code "38") (name "Net-(IC1B-USBRBIAS)") (class "Default")
      (node (ref "IC1") (pin "63") (pinfunction "USBRBIAS_63") (pintype "bidirectional"))
      (node (ref "R3") (pin "2") (pinfunction "2_2") (pintype "passive"))
    )
    (net (code "39") (name "Net-(IC1B-VBUS_DET)") (class "Default")
      (node (ref "IC1") (pin "11") (pinfunction "VBUS_DET_11") (pintype "bidirectional"))
      (node (ref "R4") (pin "1") (pinfunction "1_1") (pintype "passive"))
    )
    (net (code "40") (name "Net-(IC1B-XI)") (class "Default")
      (node (ref "C8") (pin "1") (pinfunction "1_1") (pintype "passive"))
      (node (ref "IC1") (pin "61") (pinfunction "XI_61") (pintype "bidirectional"))
      (node (ref "R2") (pin "2") (pinfunction "2_2") (pintype "passive"))
      (node (ref "XT1") (pin "3") (pinfunction "3_3") (pintype "passive"))
    )
    (net (code "41") (name "Net-(IC1B-XO)") (class "Default")
      (node (ref "C5") (pin "1") (pinfunction "1_1") (pintype "passive"))
      (node (ref "IC1") (pin "60") (pinfunction "XO_60") (pintype "bidirectional"))
      (node (ref "R2") (pin "1") (pinfunction "1_1") (pintype "passive"))
      (node (ref "XT1") (pin "1") (pinfunction "1_1") (pintype "passive"))
    )
    (net (code "42") (name "Net-(IC1C-AUTOMDIX_EN)") (class "Default")
      (node (ref "IC1") (pin "41") (pinfunction "AUTOMDIX_EN_41") (pintype "bidirectional"))
      (node (ref "R11") (pin "1") (pinfunction "1_1") (pintype "passive"))
    )
    (net (code "43") (name "Net-(IC1C-EXRES)") (class "Default")
      (node (ref "IC1") (pin "50") (pinfunction "EXRES_50") (pintype "bidirectional"))
      (node (ref "R8") (pin "2") (pinfunction "2_2") (pintype "passive"))
    )
    (net (code "44") (name "Net-(IC1C-NLNKA_LED)") (class "Default")
      (node (ref "IC1") (pin "21") (pinfunction "NLNKA_LED_21") (pintype "bidirectional"))
      (node (ref "R16") (pin "2") (pinfunction "2_2") (pintype "passive"))
    )
    (net (code "45") (name "Net-(IC1C-NSPD_LED)") (class "Default")
      (node (ref "IC1") (pin "22") (pinfunction "NSPD_LED_22") (pintype "bidirectional"))
      (node (ref "R15") (pin "2") (pinfunction "2_2") (pintype "passive"))
    )
    (net (code "46") (name "Net-(IC5D-EEDATA)") (class "Default")
      (node (ref "IC5") (pin "61") (pinfunction "EEDATA_61") (pintype "bidirectional"))
      (node (ref "R21") (pin "2") (pinfunction "2_2") (pintype "passive"))
    )
    (net (code "47") (name "Net-(IC5D-REF)") (class "Default")
      (node (ref "IC5") (pin "6") (pinfunction "REF_6") (pintype "input"))
      (node (ref "R19") (pin "2") (pinfunction "2_2") (pintype "passive"))
    )
    (net (code "48") (name "Net-(IC5D-XTIN)") (class "Default")
      (node (ref "C37") (pin "1") (pinfunction "1_1") (pintype "passive"))
      (node (ref "IC5") (pin "2") (pinfunction "XTIN_2") (pintype "input"))
      (node (ref "XT3") (pin "1") (pinfunction "1_1") (pintype "passive"))
    )
    (net (code "49") (name "Net-(IC5D-XTOUT)") (class "Default")
      (node (ref "C38") (pin "1") (pinfunction "1_1") (pintype "passive"))
      (node (ref "IC5") (pin "3") (pinfunction "XTOUT_3") (pintype "output"))
      (node (ref "XT3") (pin "3") (pinfunction "3_3") (pintype "passive"))
    )
    (net (code "50") (name "Net-(JP2-Pad1)") (class "Default")
      (node (ref "JP2") (pin "1") (pinfunction "1_1") (pintype "passive"))
      (node (ref "USB_E") (pin "1") (pinfunction "1_1") (pintype "passive"))
    )
    (net (code "51") (name "Net-(LAN-CTR)") (class "Default")
      (node (ref "C28") (pin "1") (pinfunction "1_1") (pintype "passive"))
      (node (ref "LAN") (pin "4") (pinfunction "CTT_4") (pintype "bidirectional"))
      (node (ref "LAN") (pin "5") (pinfunction "CTR_5") (pintype "bidirectional"))
      (node (ref "R14") (pin "1") (pinfunction "1_1") (pintype "passive"))
    )
    (net (code "52") (name "Net-(OK1-A)") (class "Default")
      (node (ref "OK1") (pin "1") (pinfunction "A_1") (pintype "passive"))
      (node (ref "R30") (pin "1") (pinfunction "1_1") (pintype "passive"))
    )
    (net (code "53") (name "Net-(OK1-EMIT)") (class "Default")
      (node (ref "OK1") (pin "3") (pinfunction "EMIT_3") (pintype "passive"))
      (node (ref "R36") (pin "2") (pinfunction "2_2") (pintype "passive"))
    )
    (net (code "54") (name "Net-(ON-PadC)") (class "Default")
      (node (ref "ON") (pin "C") (pinfunction "C_C") (pintype "passive"))
      (node (ref "R22") (pin "2") (pinfunction "2_2") (pintype "passive"))
    )
    (net (code "55") (name "Net-(OPT-Pad1)") (class "Default")
      (node (ref "OPT") (pin "1") (pinfunction "1_1") (pintype "passive"))
      (node (ref "R39") (pin "1") (pinfunction "1_1") (pintype "passive"))
    )
    (net (code "56") (name "Net-(OPT1-P$1)") (class "Default")
      (node (ref "H") (pin "1") (pinfunction "1_1") (pintype "passive"))
      (node (ref "OPT1") (pin "1") (pinfunction "P$1_1") (pintype "bidirectional"))
    )
    (net (code "57") (name "Net-(OPT1-P$3)") (class "Default")
      (node (ref "H") (pin "2") (pinfunction "2_2") (pintype "passive"))
      (node (ref "OPT1") (pin "3") (pinfunction "P$3_3") (pintype "bidirectional"))
    )
    (net (code "58") (name "Net-(PLUG-Pad1)") (class "Default")
      (node (ref "PLUG") (pin "1") (pinfunction "1_1") (pintype "bidirectional"))
      (node (ref "V_SRC") (pin "2") (pinfunction "2_2") (pintype "passive"))
    )
    (net (code "59") (name "Net-(PLUG-Pad3)") (class "Default")
      (node (ref "PLUG") (pin "3") (pinfunction "3_3") (pintype "bidirectional"))
      (node (ref "V_SEN") (pin "2") (pinfunction "2_2") (pintype "passive"))
    )
    (net (code "60") (name "Net-(PWR-Pad1)") (class "Default")
      (node (ref "PWR") (pin "1") (pinfunction "1_1") (pintype "passive"))
      (node (ref "R32") (pin "1") (pinfunction "1_1") (pintype "passive"))
    )
    (net (code "61") (name "Net-(Q1-D)") (class "Default")
      (node (ref "Q1") (pin "3") (pinfunction "D_3") (pintype "passive"))
      (node (ref "USB1") (pin "4") (pinfunction "ID_4") (pintype "bidirectional"))
    )
    (net (code "62") (name "Net-(Q2-D)") (class "Default")
      (node (ref "Q2") (pin "3") (pinfunction "D_3") (pintype "passive"))
      (node (ref "USB2") (pin "4") (pinfunction "ID_4") (pintype "bidirectional"))
    )
    (net (code "63") (name "Net-(Q3-D)") (class "Default")
      (node (ref "FAN") (pin "2") (pinfunction "2_2") (pintype "passive"))
      (node (ref "Q3") (pin "3") (pinfunction "D_3") (pintype "passive"))
    )
    (net (code "64") (name "Net-(Q6-D)") (class "Default")
      (node (ref "LAMP") (pin "2") (pinfunction "2_2") (pintype "passive"))
      (node (ref "Q6") (pin "3") (pinfunction "D_3") (pintype "passive"))
    )
    (net (code "65") (name "Net-(Q6-G)") (class "Default")
      (node (ref "Q6") (pin "1") (pinfunction "G_1") (pintype "passive"))
      (node (ref "R36") (pin "1") (pinfunction "1_1") (pintype "passive"))
      (node (ref "R38") (pin "2") (pinfunction "2_2") (pintype "passive"))
    )
    (net (code "66") (name "Net-(U1-AREF)") (class "Default")
      (node (ref "C33") (pin "2") (pinfunction "2_2") (pintype "passive"))
      (node (ref "U1") (pin "20") (pinfunction "AREF_20") (pintype "input"))
    )
    (net (code "67") (name "RST1") (class "Default")
      (node (ref "IC1") (pin "12") (pinfunction "NRESET_12") (pintype "bidirectional"))
      (node (ref "IC2") (pin "11") (pinfunction "~{RESET}_11") (pintype "input"))
      (node (ref "IC5") (pin "14") (pinfunction "RESET#_14") (pintype "input"))
      (node (ref "R7") (pin "1") (pinfunction "1_1") (pintype "passive"))
      (node (ref "RST1") (pin "TP") (pinfunction "TP_TP") (pintype "input"))
    )
    (net (code "68") (name "RST2") (class "Default")
      (node (ref "C44") (pin "2") (pinfunction "2_2") (pintype "passive"))
      (node (ref "ICSP") (pin "5") (pinfunction "5_5") (pintype "passive"))
      (node (ref "R42") (pin "2") (pinfunction "2_2") (pintype "passive"))
      (node (ref "RST2") (pin "TP") (pinfunction "TP_TP") (pintype "input"))
      (node (ref "U1") (pin "29") (pinfunction "PC6_29") (pintype "bidirectional"))
    )
    (net (code "69") (name "RX3") (class "Default")
      (node (ref "IC5") (pin "39") (pinfunction "DB1/RXD_39") (pintype "bidirectional"))
      (node (ref "UART_D") (pin "3") (pinfunction "3_3") (pintype "passive"))
    )
    (net (code "70") (name "RXN") (class "Default")
      (node (ref "C24") (pin "1") (pinfunction "1_1") (pintype "passive"))
      (node (ref "IC1") (pin "53") (pinfunction "RXN_53") (pintype "bidirectional"))
      (node (ref "LAN") (pin "6") (pinfunction "RD-_6") (pintype "bidirectional"))
      (node (ref "R9") (pin "1") (pinfunction "1_1") (pintype "passive"))
    )
    (net (code "71") (name "RXP") (class "Default")
      (node (ref "C25") (pin "1") (pinfunction "1_1") (pintype "passive"))
      (node (ref "IC1") (pin "52") (pinfunction "RXP_52") (pintype "bidirectional"))
      (node (ref "LAN") (pin "3") (pinfunction "RD+_3") (pintype "bidirectional"))
      (node (ref "R10") (pin "1") (pinfunction "1_1") (pintype "passive"))
    )
    (net (code "72") (name "RX_ARD") (class "Default")
      (node (ref "IC5") (pin "27") (pinfunction "DB1/RXD_27") (pintype "bidirectional"))
      (node (ref "Q5") (pin "2") (pinfunction "S_2") (pintype "passive"))
      (node (ref "R35") (pin "2") (pinfunction "2_2") (pintype "passive"))
    )
    (net (code "73") (name "RX_D") (class "Default")
      (node (ref "IC5") (pin "52") (pinfunction "DB1/RXD_52") (pintype "bidirectional"))
      (node (ref "IC9") (pin "9") (pinfunction "DB_9") (pintype "bidirectional"))
      (node (ref "RX_4") (pin "TP") (pinfunction "TP_TP") (pintype "input"))
    )
    (net (code "74") (name "RX_MCU") (class "Default")
      (node (ref "Q4") (pin "3") (pinfunction "D_3") (pintype "passive"))
      (node (ref "R40") (pin "2") (pinfunction "2_2") (pintype "passive"))
      (node (ref "U1") (pin "30") (pinfunction "PD0_30") (pintype "bidirectional"))
    )
    (net (code "75") (name "RX_T") (class "Default")
      (node (ref "IC2") (pin "4") (pinfunction "RXD_4") (pintype "input"))
      (node (ref "IC5") (pin "16") (pinfunction "DB0/TXD_16") (pintype "bidirectional"))
      (node (ref "TX_1") (pin "TP") (pinfunction "TP_TP") (pintype "input"))
    )
    (net (code "76") (name "S1A") (class "Default")
      (node (ref "IC9") (pin "4") (pinfunction "S1A_4") (pintype "bidirectional"))
      (node (ref "UART_5V") (pin "4") (pinfunction "4_4") (pintype "passive"))
    )
    (net (code "77") (name "S1B") (class "Default")
      (node (ref "IC9") (pin "13") (pinfunction "S1B_13") (pintype "bidirectional"))
      (node (ref "UART_5V") (pin "6") (pinfunction "6_6") (pintype "passive"))
    )
    (net (code "78") (name "S2A") (class "Default")
      (node (ref "IC9") (pin "5") (pinfunction "S2A_5") (pintype "bidirectional"))
      (node (ref "UART_5V") (pin "3") (pinfunction "3_3") (pintype "passive"))
    )
    (net (code "79") (name "S2B") (class "Default")
      (node (ref "IC9") (pin "12") (pinfunction "S2B_12") (pintype "bidirectional"))
      (node (ref "UART_5V") (pin "5") (pinfunction "5_5") (pintype "passive"))
    )
    (net (code "80") (name "S3A") (class "Default")
      (node (ref "IC9") (pin "6") (pinfunction "S3A_6") (pintype "bidirectional"))
      (node (ref "UART_3V") (pin "4") (pinfunction "4_4") (pintype "passive"))
    )
    (net (code "81") (name "S3B") (class "Default")
      (node (ref "IC9") (pin "11") (pinfunction "S3B_11") (pintype "bidirectional"))
      (node (ref "UART_3V") (pin "6") (pinfunction "6_6") (pintype "passive"))
    )
    (net (code "82") (name "S4A") (class "Default")
      (node (ref "IC9") (pin "7") (pinfunction "S4A_7") (pintype "bidirectional"))
      (node (ref "UART_3V") (pin "3") (pinfunction "3_3") (pintype "passive"))
    )
    (net (code "83") (name "S4B") (class "Default")
      (node (ref "IC9") (pin "10") (pinfunction "S4B_10") (pintype "bidirectional"))
      (node (ref "UART_3V") (pin "5") (pinfunction "5_5") (pintype "passive"))
    )
    (net (code "84") (name "SCL") (class "Default")
      (node (ref "I2C") (pin "2") (pinfunction "2_2") (pintype "passive"))
      (node (ref "IC6") (pin "4") (pinfunction "SCL_4") (pintype "bidirectional"))
      (node (ref "R27") (pin "2") (pinfunction "2_2") (pintype "passive"))
      (node (ref "U1") (pin "28") (pinfunction "PC5_28") (pintype "bidirectional"))
    )
    (net (code "85") (name "SDA") (class "Default")
      (node (ref "I2C") (pin "1") (pinfunction "1_1") (pintype "passive"))
      (node (ref "IC6") (pin "5") (pinfunction "SDA_5") (pintype "bidirectional"))
      (node (ref "R23") (pin "2") (pinfunction "2_2") (pintype "passive"))
      (node (ref "U1") (pin "27") (pinfunction "PC4_27") (pintype "bidirectional"))
    )
    (net (code "86") (name "T2_USBD+") (class "Default")
      (node (ref "IC2") (pin "8") (pinfunction "USBDP_8") (pintype "input"))
      (node (ref "USB2") (pin "3") (pinfunction "D+_3") (pintype "bidirectional"))
    )
    (net (code "87") (name "T2_USBD-") (class "Default")
      (node (ref "IC2") (pin "9") (pinfunction "USBDM_9") (pintype "input"))
      (node (ref "USB2") (pin "2") (pinfunction "D-_2") (pintype "bidirectional"))
    )
    (net (code "88") (name "TX3") (class "Default")
      (node (ref "IC5") (pin "38") (pinfunction "DB0/TXD_38") (pintype "bidirectional"))
      (node (ref "UART_D") (pin "2") (pinfunction "2_2") (pintype "passive"))
    )
    (net (code "89") (name "TXN") (class "Default")
      (node (ref "C26") (pin "1") (pinfunction "1_1") (pintype "passive"))
      (node (ref "IC1") (pin "56") (pinfunction "TXN_56") (pintype "bidirectional"))
      (node (ref "LAN") (pin "2") (pinfunction "TD-_2") (pintype "bidirectional"))
      (node (ref "R12") (pin "1") (pinfunction "1_1") (pintype "passive"))
    )
    (net (code "90") (name "TXP") (class "Default")
      (node (ref "C27") (pin "1") (pinfunction "1_1") (pintype "passive"))
      (node (ref "IC1") (pin "55") (pinfunction "TXP_55") (pintype "bidirectional"))
      (node (ref "LAN") (pin "1") (pinfunction "TD+_1") (pintype "bidirectional"))
      (node (ref "R13") (pin "1") (pinfunction "1_1") (pintype "passive"))
    )
    (net (code "91") (name "TX_ARD") (class "Default")
      (node (ref "IC5") (pin "26") (pinfunction "DB0/TXD_26") (pintype "bidirectional"))
      (node (ref "Q4") (pin "2") (pinfunction "S_2") (pintype "passive"))
      (node (ref "R34") (pin "2") (pinfunction "2_2") (pintype "passive"))
    )
    (net (code "92") (name "TX_D") (class "Default")
      (node (ref "IC5") (pin "48") (pinfunction "DB0/TXD_48") (pintype "bidirectional"))
      (node (ref "IC9") (pin "8") (pinfunction "DA_8") (pintype "bidirectional"))
      (node (ref "TX_4") (pin "TP") (pinfunction "TP_TP") (pintype "input"))
    )
    (net (code "93") (name "TX_MCU") (class "Default")
      (node (ref "Q5") (pin "3") (pinfunction "D_3") (pintype "passive"))
      (node (ref "R41") (pin "2") (pinfunction "2_2") (pintype "passive"))
      (node (ref "U1") (pin "31") (pinfunction "PD1_31") (pintype "bidirectional"))
    )
    (net (code "94") (name "TX_T") (class "Default")
      (node (ref "IC2") (pin "1") (pinfunction "TXD_1") (pintype "output"))
      (node (ref "IC5") (pin "17") (pinfunction "DB1/RXD_17") (pintype "bidirectional"))
      (node (ref "RX_1") (pin "TP") (pinfunction "TP_TP") (pintype "input"))
    )
    (net (code "95") (name "USB0_D+") (class "Default")
      (node (ref "IC1") (pin "59") (pinfunction "USBDP0_59") (pintype "bidirectional"))
      (node (ref "USB1") (pin "3") (pinfunction "D+_3") (pintype "bidirectional"))
    )
    (net (code "96") (name "USB0_D-") (class "Default")
      (node (ref "IC1") (pin "58") (pinfunction "USBDM0_58") (pintype "bidirectional"))
      (node (ref "USB1") (pin "2") (pinfunction "D-_2") (pintype "bidirectional"))
    )
    (net (code "97") (name "USB1_D+") (class "Default")
      (node (ref "IC1") (pin "2") (pinfunction "USBDP2_2") (pintype "bidirectional"))
      (node (ref "USB_PORTS") (pin "6") (pinfunction "6_6") (pintype "passive"))
    )
    (net (code "98") (name "USB1_D-") (class "Default")
      (node (ref "IC1") (pin "1") (pinfunction "USBDM2_1") (pintype "bidirectional"))
      (node (ref "USB_PORTS") (pin "4") (pinfunction "4_4") (pintype "passive"))
    )
    (net (code "99") (name "USB2_D+") (class "Default")
      (node (ref "IC1") (pin "4") (pinfunction "USBDP3_4") (pintype "bidirectional"))
      (node (ref "USB_PORTS") (pin "5") (pinfunction "5_5") (pintype "passive"))
    )
    (net (code "100") (name "USB2_D-") (class "Default")
      (node (ref "IC1") (pin "3") (pinfunction "USBDM3_3") (pintype "bidirectional"))
      (node (ref "USB_PORTS") (pin "3") (pinfunction "3_3") (pintype "passive"))
    )
    (net (code "101") (name "USB3_D+") (class "Default")
      (node (ref "IC1") (pin "7") (pinfunction "USBDP4_7") (pintype "bidirectional"))
      (node (ref "IC5") (pin "8") (pinfunction "USBDP_8") (pintype "input"))
    )
    (net (code "102") (name "USB3_D-") (class "Default")
      (node (ref "IC1") (pin "6") (pinfunction "USBDM4_6") (pintype "bidirectional"))
      (node (ref "IC5") (pin "7") (pinfunction "USBDM_7") (pintype "input"))
    )
    (net (code "103") (name "USB4_D+") (class "Default")
      (node (ref "IC1") (pin "9") (pinfunction "USBDP5_9") (pintype "bidirectional"))
      (node (ref "USB_E") (pin "3") (pinfunction "3_3") (pintype "passive"))
    )
    (net (code "104") (name "USB4_D-") (class "Default")
      (node (ref "IC1") (pin "8") (pinfunction "USBDM5_8") (pintype "bidirectional"))
      (node (ref "USB_E") (pin "2") (pinfunction "2_2") (pintype "passive"))
    )
    (net (code "105") (name "USB_PLL") (class "Default")
      (node (ref "C19") (pin "1") (pinfunction "1_1") (pintype "passive"))
      (node (ref "IC1") (pin "62") (pinfunction "VDD18USBPLL_62") (pintype "bidirectional"))
      (node (ref "R5") (pin "1") (pinfunction "1_1") (pintype "passive"))
    )
    (net (code "106") (name "VCCIO") (class "Default")
      (node (ref "C39") (pin "1") (pinfunction "1_1") (pintype "passive"))
      (node (ref "C40") (pin "1") (pinfunction "1_1") (pintype "passive"))
      (node (ref "IC6") (pin "3") (pinfunction "VCC_3") (pintype "bidirectional"))
      (node (ref "ICSP") (pin "2") (pinfunction "2_2") (pintype "passive"))
      (node (ref "PIR") (pin "1") (pinfunction "1_1") (pintype "passive"))
      (node (ref "R23") (pin "1") (pinfunction "1_1") (pintype "passive"))
      (node (ref "R27") (pin "1") (pinfunction "1_1") (pintype "passive"))
      (node (ref "R31") (pin "1") (pinfunction "1_1") (pintype "passive"))
      (node (ref "R37") (pin "1") (pinfunction "1_1") (pintype "passive"))
      (node (ref "R39") (pin "2") (pinfunction "2_2") (pintype "passive"))
      (node (ref "R40") (pin "1") (pinfunction "1_1") (pintype "passive"))
      (node (ref "R41") (pin "1") (pinfunction "1_1") (pintype "passive"))
      (node (ref "R42") (pin "1") (pinfunction "1_1") (pintype "passive"))
      (node (ref "SL6") (pin "1") (pinfunction "1_1") (pintype "passive"))
      (node (ref "SW1") (pin "2") (pinfunction "2_2") (pintype "bidirectional"))
      (node (ref "SW1") (pin "5") (pinfunction "5_5") (pintype "bidirectional"))
      (node (ref "U1") (pin "18") (pinfunction "AVCC_18") (pintype "power_in"))
      (node (ref "U1") (pin "4") (pinfunction "VCC_2_4") (pintype "power_in"))
      (node (ref "U1") (pin "6") (pinfunction "VCC_6") (pintype "power_in"))
    )
    (net (code "107") (name "VPHY") (class "Default")
      (node (ref "C35") (pin "1") (pinfunction "1_1") (pintype "passive"))
      (node (ref "C36") (pin "1") (pinfunction "1_1") (pintype "passive"))
      (node (ref "IC5") (pin "4") (pinfunction "VPHY_4") (pintype "power_in"))
      (node (ref "R20") (pin "1") (pinfunction "1_1") (pintype "passive"))
    )
    (net (code "108") (name "VPLL") (class "Default")
      (node (ref "C30") (pin "1") (pinfunction "1_1") (pintype "passive"))
      (node (ref "C32") (pin "1") (pinfunction "1_1") (pintype "passive"))
      (node (ref "IC5") (pin "9") (pinfunction "VPLL_9") (pintype "power_in"))
      (node (ref "R17") (pin "1") (pinfunction "1_1") (pintype "passive"))
    )
    (net (code "109") (name "X0_ARD") (class "Default")
      (node (ref "C31") (pin "1") (pinfunction "1_1") (pintype "passive"))
      (node (ref "R18") (pin "1") (pinfunction "1_1") (pintype "passive"))
      (node (ref "U1") (pin "7") (pinfunction "PB6_7") (pintype "bidirectional"))
      (node (ref "XT2") (pin "1") (pinfunction "1_1") (pintype "passive"))
    )
    (net (code "110") (name "X1_ARD") (class "Default")
      (node (ref "C34") (pin "1") (pinfunction "1_1") (pintype "passive"))
      (node (ref "R18") (pin "2") (pinfunction "2_2") (pintype "passive"))
      (node (ref "U1") (pin "8") (pinfunction "PB7_8") (pintype "bidirectional"))
      (node (ref "XT2") (pin "3") (pinfunction "3_3") (pintype "passive"))
    )
    (net (code "111") (name "YEL") (class "Default")
      (node (ref "LAN") (pin "Y2") (pinfunction "Y-_Y2") (pintype "bidirectional"))
      (node (ref "R15") (pin "1") (pinfunction "1_1") (pintype "passive"))
    )
    (net (code "112") (name "unconnected-(IC1A-CLK24_OUT-Pad45)") (class "Default")
      (node (ref "IC1") (pin "45") (pinfunction "CLK24_OUT_45") (pintype "bidirectional"))
    )
    (net (code "113") (name "unconnected-(IC1A-EECLK-Pad23)") (class "Default")
      (node (ref "IC1") (pin "23") (pinfunction "EECLK_23") (pintype "bidirectional"))
    )
    (net (code "114") (name "unconnected-(IC1A-EECS-Pad24)") (class "Default")
      (node (ref "IC1") (pin "24") (pinfunction "EECS_24") (pintype "bidirectional"))
    )
    (net (code "115") (name "unconnected-(IC1A-EEDI-Pad26)") (class "Default")
      (node (ref "IC1") (pin "26") (pinfunction "EEDI_26") (pintype "bidirectional"))
    )
    (net (code "116") (name "unconnected-(IC1A-EEDO-Pad25)") (class "Default")
      (node (ref "IC1") (pin "25") (pinfunction "EEDO_25") (pintype "bidirectional"))
    )
    (net (code "117") (name "unconnected-(IC1A-GPIO3-Pad35)") (class "Default")
      (node (ref "IC1") (pin "35") (pinfunction "GPIO3_35") (pintype "bidirectional"))
    )
    (net (code "118") (name "unconnected-(IC1A-GPIO4-Pad36)") (class "Default")
      (node (ref "IC1") (pin "36") (pinfunction "GPIO4_36") (pintype "bidirectional"))
    )
    (net (code "119") (name "unconnected-(IC1A-GPIO5-Pad37)") (class "Default")
      (node (ref "IC1") (pin "37") (pinfunction "GPIO5_37") (pintype "bidirectional"))
    )
    (net (code "120") (name "unconnected-(IC1A-GPIO6-Pad42)") (class "Default")
      (node (ref "IC1") (pin "42") (pinfunction "GPIO6_42") (pintype "bidirectional"))
    )
    (net (code "121") (name "unconnected-(IC1A-GPIO7-Pad43)") (class "Default")
      (node (ref "IC1") (pin "43") (pinfunction "GPIO7_43") (pintype "bidirectional"))
    )
    (net (code "122") (name "unconnected-(IC1A-TCK-Pad32)") (class "Default")
      (node (ref "IC1") (pin "32") (pinfunction "TCK_32") (pintype "bidirectional"))
    )
    (net (code "123") (name "unconnected-(IC1A-TDI-Pad30)") (class "Default")
      (node (ref "IC1") (pin "30") (pinfunction "TDI_30") (pintype "bidirectional"))
    )
    (net (code "124") (name "unconnected-(IC1A-TDO-Pad31)") (class "Default")
      (node (ref "IC1") (pin "31") (pinfunction "TDO_31") (pintype "bidirectional"))
    )
    (net (code "125") (name "unconnected-(IC1A-TEST1-Pad13)") (class "Default")
      (node (ref "IC1") (pin "13") (pinfunction "TEST1_13") (pintype "bidirectional"))
    )
    (net (code "126") (name "unconnected-(IC1A-TEST4-Pad47)") (class "Default")
      (node (ref "IC1") (pin "47") (pinfunction "TEST4_47") (pintype "bidirectional"))
    )
    (net (code "127") (name "unconnected-(IC1A-TMS-Pad29)") (class "Default")
      (node (ref "IC1") (pin "29") (pinfunction "TMS_29") (pintype "bidirectional"))
    )
    (net (code "128") (name "unconnected-(IC1B-PRTCTL2-Pad14)") (class "Default")
      (node (ref "IC1") (pin "14") (pinfunction "PRTCTL2_14") (pintype "bidirectional"))
    )
    (net (code "129") (name "unconnected-(IC1B-PRTCTL3-Pad16)") (class "Default")
      (node (ref "IC1") (pin "16") (pinfunction "PRTCTL3_16") (pintype "bidirectional"))
    )
    (net (code "130") (name "unconnected-(IC1B-PRTCTL4-Pad17)") (class "Default")
      (node (ref "IC1") (pin "17") (pinfunction "PRTCTL4_17") (pintype "bidirectional"))
    )
    (net (code "131") (name "unconnected-(IC1B-PRTCTL5-Pad18)") (class "Default")
      (node (ref "IC1") (pin "18") (pinfunction "PRTCTL5_18") (pintype "bidirectional"))
    )
    (net (code "132") (name "unconnected-(IC1C-NFDX_LED-Pad20)") (class "Default")
      (node (ref "IC1") (pin "20") (pinfunction "NFDX_LED_20") (pintype "bidirectional"))
    )
    (net (code "133") (name "unconnected-(IC2-CBUS0-Pad15)") (class "Default")
      (node (ref "IC2") (pin "15") (pinfunction "CBUS0_15") (pintype "bidirectional"))
    )
    (net (code "134") (name "unconnected-(IC2-CBUS1-Pad14)") (class "Default")
      (node (ref "IC2") (pin "14") (pinfunction "CBUS1_14") (pintype "bidirectional"))
    )
    (net (code "135") (name "unconnected-(IC2-CBUS2-Pad7)") (class "Default")
      (node (ref "IC2") (pin "7") (pinfunction "CBUS2_7") (pintype "bidirectional"))
    )
    (net (code "136") (name "unconnected-(IC2-CBUS3-Pad16)") (class "Default")
      (node (ref "IC2") (pin "16") (pinfunction "CBUS3_16") (pintype "bidirectional"))
    )
    (net (code "137") (name "unconnected-(IC2-~{CTS}-Pad6)") (class "Default")
      (node (ref "IC2") (pin "6") (pinfunction "~{CTS}_6") (pintype "input"))
    )
    (net (code "138") (name "unconnected-(IC2-~{RTS}-Pad2)") (class "Default")
      (node (ref "IC2") (pin "2") (pinfunction "~{RTS}_2") (pintype "output"))
    )
    (net (code "139") (name "unconnected-(IC5A-DB2{slash}RTS-Pad18)") (class "Default")
      (node (ref "IC5") (pin "18") (pinfunction "DB2/RTS_18") (pintype "bidirectional"))
    )
    (net (code "140") (name "unconnected-(IC5A-DB3{slash}CTS-Pad19)") (class "Default")
      (node (ref "IC5") (pin "19") (pinfunction "DB3/CTS_19") (pintype "bidirectional"))
    )
    (net (code "141") (name "unconnected-(IC5A-DB4{slash}DTR-Pad21)") (class "Default")
      (node (ref "IC5") (pin "21") (pinfunction "DB4/DTR_21") (pintype "bidirectional"))
    )
    (net (code "142") (name "unconnected-(IC5A-DB5{slash}DSR-Pad22)") (class "Default")
      (node (ref "IC5") (pin "22") (pinfunction "DB5/DSR_22") (pintype "bidirectional"))
    )
    (net (code "143") (name "unconnected-(IC5A-DB6{slash}DCD-Pad23)") (class "Default")
      (node (ref "IC5") (pin "23") (pinfunction "DB6/DCD_23") (pintype "bidirectional"))
    )
    (net (code "144") (name "unconnected-(IC5A-DB7{slash}RI-Pad24)") (class "Default")
      (node (ref "IC5") (pin "24") (pinfunction "DB7/RI_24") (pintype "bidirectional"))
    )
    (net (code "145") (name "unconnected-(IC5B-DB2{slash}RTS-Pad28)") (class "Default")
      (node (ref "IC5") (pin "28") (pinfunction "DB2/RTS_28") (pintype "bidirectional"))
    )
    (net (code "146") (name "unconnected-(IC5B-DB3{slash}CTS-Pad29)") (class "Default")
      (node (ref "IC5") (pin "29") (pinfunction "DB3/CTS_29") (pintype "bidirectional"))
    )
    (net (code "147") (name "unconnected-(IC5B-DB5{slash}DSR-Pad32)") (class "Default")
      (node (ref "IC5") (pin "32") (pinfunction "DB5/DSR_32") (pintype "bidirectional"))
    )
    (net (code "148") (name "unconnected-(IC5B-DB6{slash}DCD-Pad33)") (class "Default")
      (node (ref "IC5") (pin "33") (pinfunction "DB6/DCD_33") (pintype "bidirectional"))
    )
    (net (code "149") (name "unconnected-(IC5B-DB7{slash}RI-Pad34)") (class "Default")
      (node (ref "IC5") (pin "34") (pinfunction "DB7/RI_34") (pintype "bidirectional"))
    )
    (net (code "150") (name "unconnected-(IC5C-DB2{slash}RTS-Pad40)") (class "Default")
      (node (ref "IC5") (pin "40") (pinfunction "DB2/RTS_40") (pintype "bidirectional"))
    )
    (net (code "151") (name "unconnected-(IC5C-DB3{slash}CTS-Pad41)") (class "Default")
      (node (ref "IC5") (pin "41") (pinfunction "DB3/CTS_41") (pintype "bidirectional"))
    )
    (net (code "152") (name "unconnected-(IC5C-DB4{slash}DTR-Pad43)") (class "Default")
      (node (ref "IC5") (pin "43") (pinfunction "DB4/DTR_43") (pintype "bidirectional"))
    )
    (net (code "153") (name "unconnected-(IC5C-DB5{slash}DSR-Pad44)") (class "Default")
      (node (ref "IC5") (pin "44") (pinfunction "DB5/DSR_44") (pintype "bidirectional"))
    )
    (net (code "154") (name "unconnected-(IC5C-DB6{slash}DCD-Pad45)") (class "Default")
      (node (ref "IC5") (pin "45") (pinfunction "DB6/DCD_45") (pintype "bidirectional"))
    )
    (net (code "155") (name "unconnected-(IC5C-DB7{slash}RI-Pad46)") (class "Default")
      (node (ref "IC5") (pin "46") (pinfunction "DB7/RI_46") (pintype "bidirectional"))
    )
    (net (code "156") (name "unconnected-(IC5D-EECLK-Pad62)") (class "Default")
      (node (ref "IC5") (pin "62") (pinfunction "EECLK_62") (pintype "output"))
    )
    (net (code "157") (name "unconnected-(IC5D-EECS-Pad63)") (class "Default")
      (node (ref "IC5") (pin "63") (pinfunction "EECS_63") (pintype "bidirectional"))
    )
    (net (code "158") (name "unconnected-(IC5D-PWREN#-Pad60)") (class "Default")
      (node (ref "IC5") (pin "60") (pinfunction "PWREN#_60") (pintype "output"))
    )
    (net (code "159") (name "unconnected-(IC5D-SUSPEND#-Pad36)") (class "Default")
      (node (ref "IC5") (pin "36") (pinfunction "SUSPEND#_36") (pintype "output"))
    )
    (net (code "160") (name "unconnected-(IC5E-DB2{slash}RTS-Pad53)") (class "Default")
      (node (ref "IC5") (pin "53") (pinfunction "DB2/RTS_53") (pintype "bidirectional"))
    )
    (net (code "161") (name "unconnected-(IC5E-DB3{slash}CTS-Pad54)") (class "Default")
      (node (ref "IC5") (pin "54") (pinfunction "DB3/CTS_54") (pintype "bidirectional"))
    )
    (net (code "162") (name "unconnected-(IC5E-DB4{slash}DTR-Pad55)") (class "Default")
      (node (ref "IC5") (pin "55") (pinfunction "DB4/DTR_55") (pintype "bidirectional"))
    )
    (net (code "163") (name "unconnected-(IC5E-DB5{slash}DSR-Pad57)") (class "Default")
      (node (ref "IC5") (pin "57") (pinfunction "DB5/DSR_57") (pintype "bidirectional"))
    )
    (net (code "164") (name "unconnected-(IC5E-DB6{slash}DCD-Pad58)") (class "Default")
      (node (ref "IC5") (pin "58") (pinfunction "DB6/DCD_58") (pintype "bidirectional"))
    )
    (net (code "165") (name "unconnected-(IC5E-DB7{slash}RI-Pad59)") (class "Default")
      (node (ref "IC5") (pin "59") (pinfunction "DB7/RI_59") (pintype "bidirectional"))
    )
    (net (code "166") (name "unconnected-(IC7-C_SENSE-Pad5)") (class "Default")
      (node (ref "IC7") (pin "5") (pinfunction "C_SENSE_5") (pintype "bidirectional"))
    )
    (net (code "167") (name "unconnected-(IC7-SEL-Pad4)") (class "Default")
      (node (ref "IC7") (pin "4") (pinfunction "SEL_4") (pintype "bidirectional"))
    )
    (net (code "168") (name "unconnected-(IC7-SEN-Pad2)") (class "Default")
      (node (ref "IC7") (pin "2") (pinfunction "SEN_2") (pintype "bidirectional"))
    )
    (net (code "169") (name "unconnected-(IC8-C_SENSE-Pad5)") (class "Default")
      (node (ref "IC8") (pin "5") (pinfunction "C_SENSE_5") (pintype "bidirectional"))
    )
    (net (code "170") (name "unconnected-(IC8-SEL-Pad4)") (class "Default")
      (node (ref "IC8") (pin "4") (pinfunction "SEL_4") (pintype "bidirectional"))
    )
    (net (code "171") (name "unconnected-(IC8-SEN-Pad2)") (class "Default")
      (node (ref "IC8") (pin "2") (pinfunction "SEN_2") (pintype "bidirectional"))
    )
  )
)
